# stm32-d40-platform.net
KiCad netlist of a schematic drawn in EAGLE
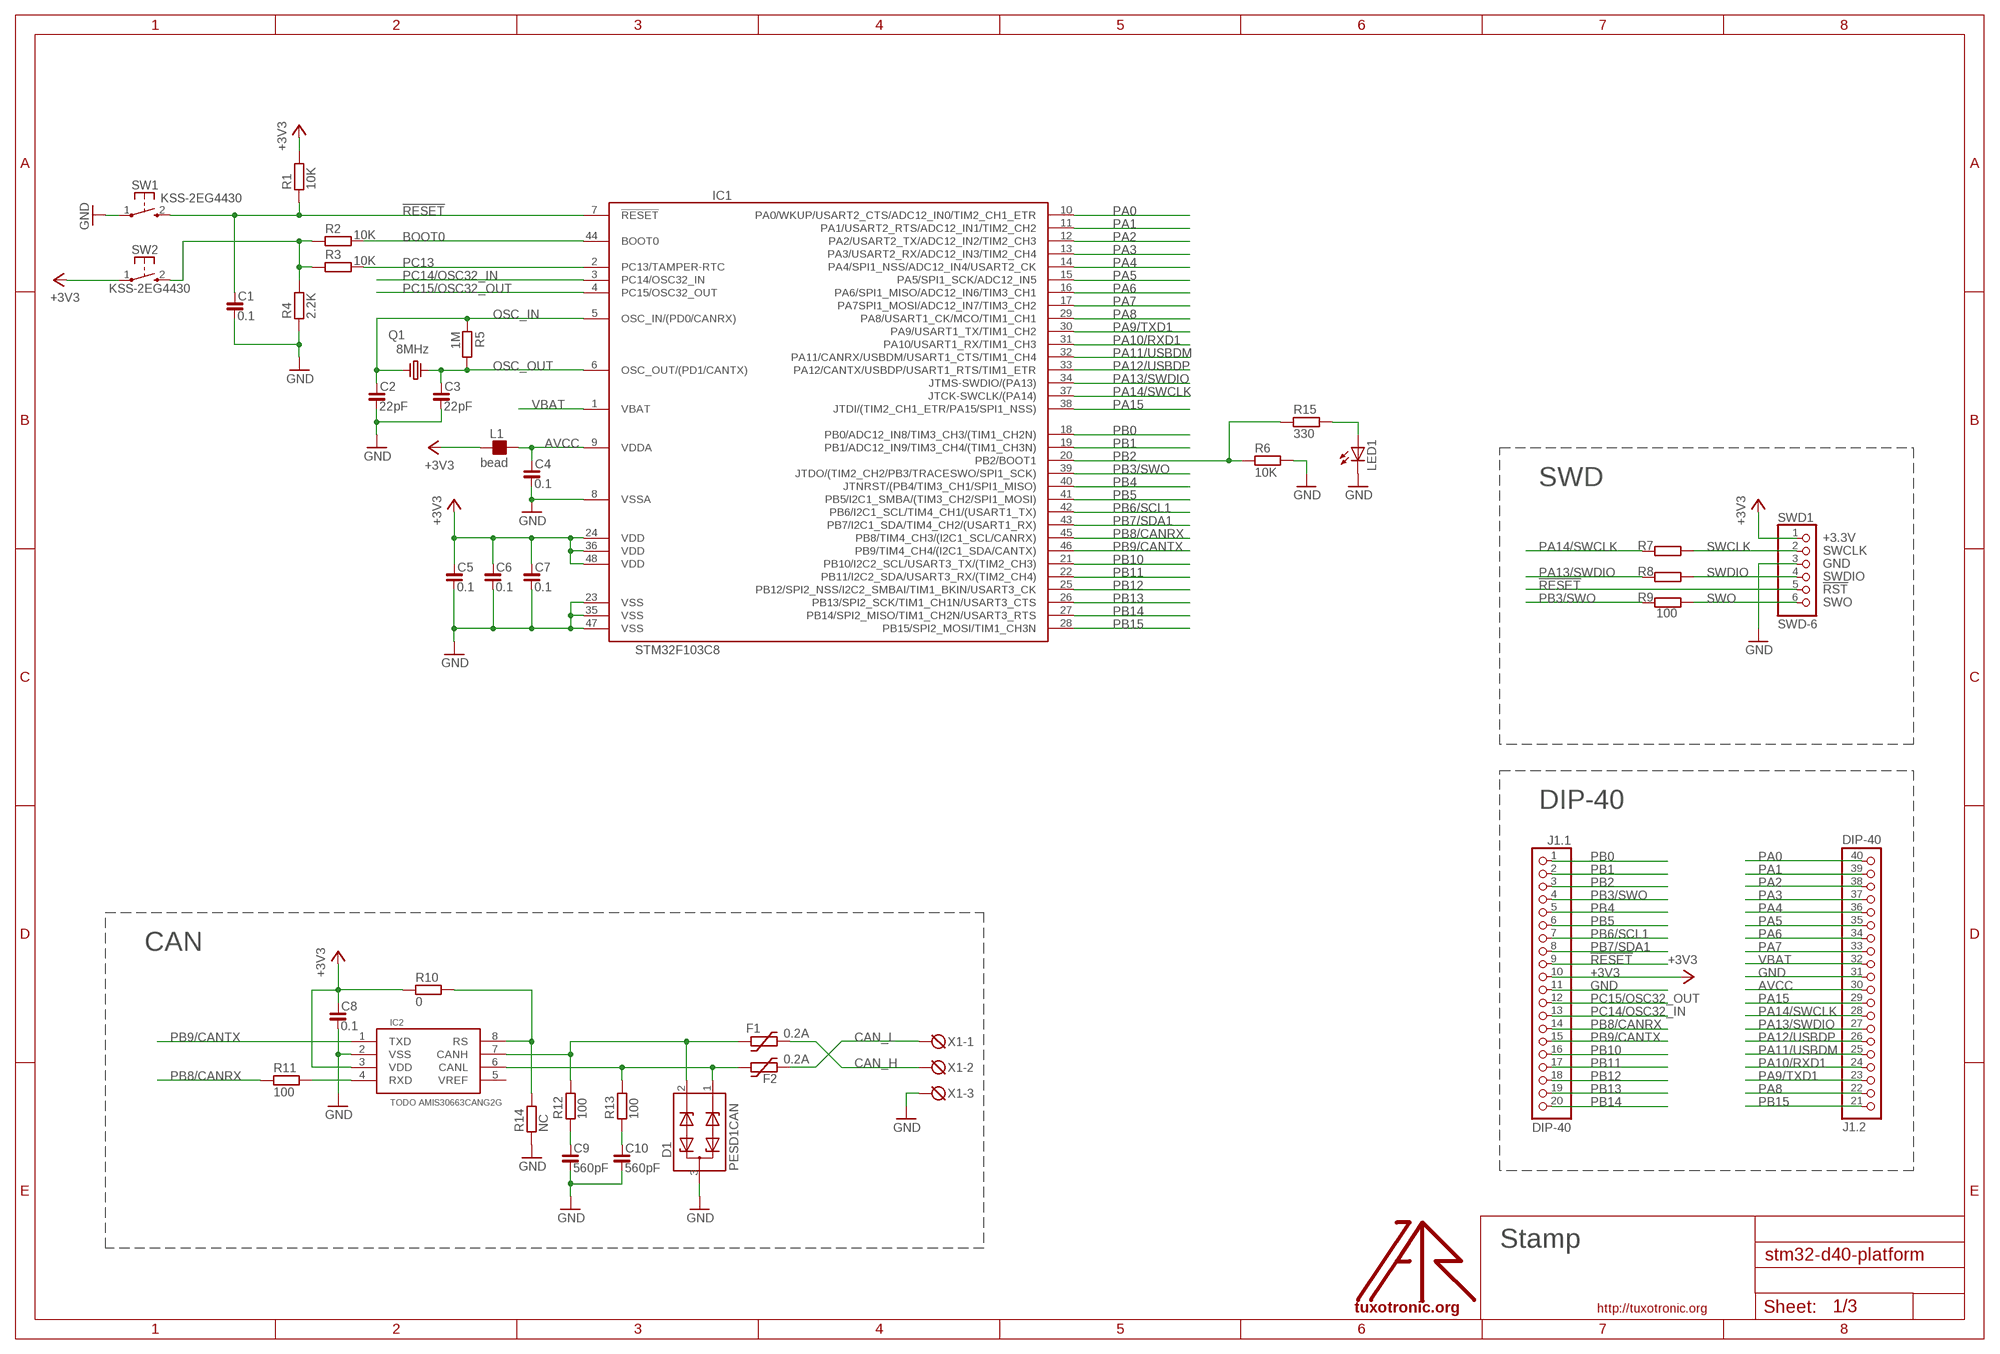
[diagram p0: schematic, sheet 1]
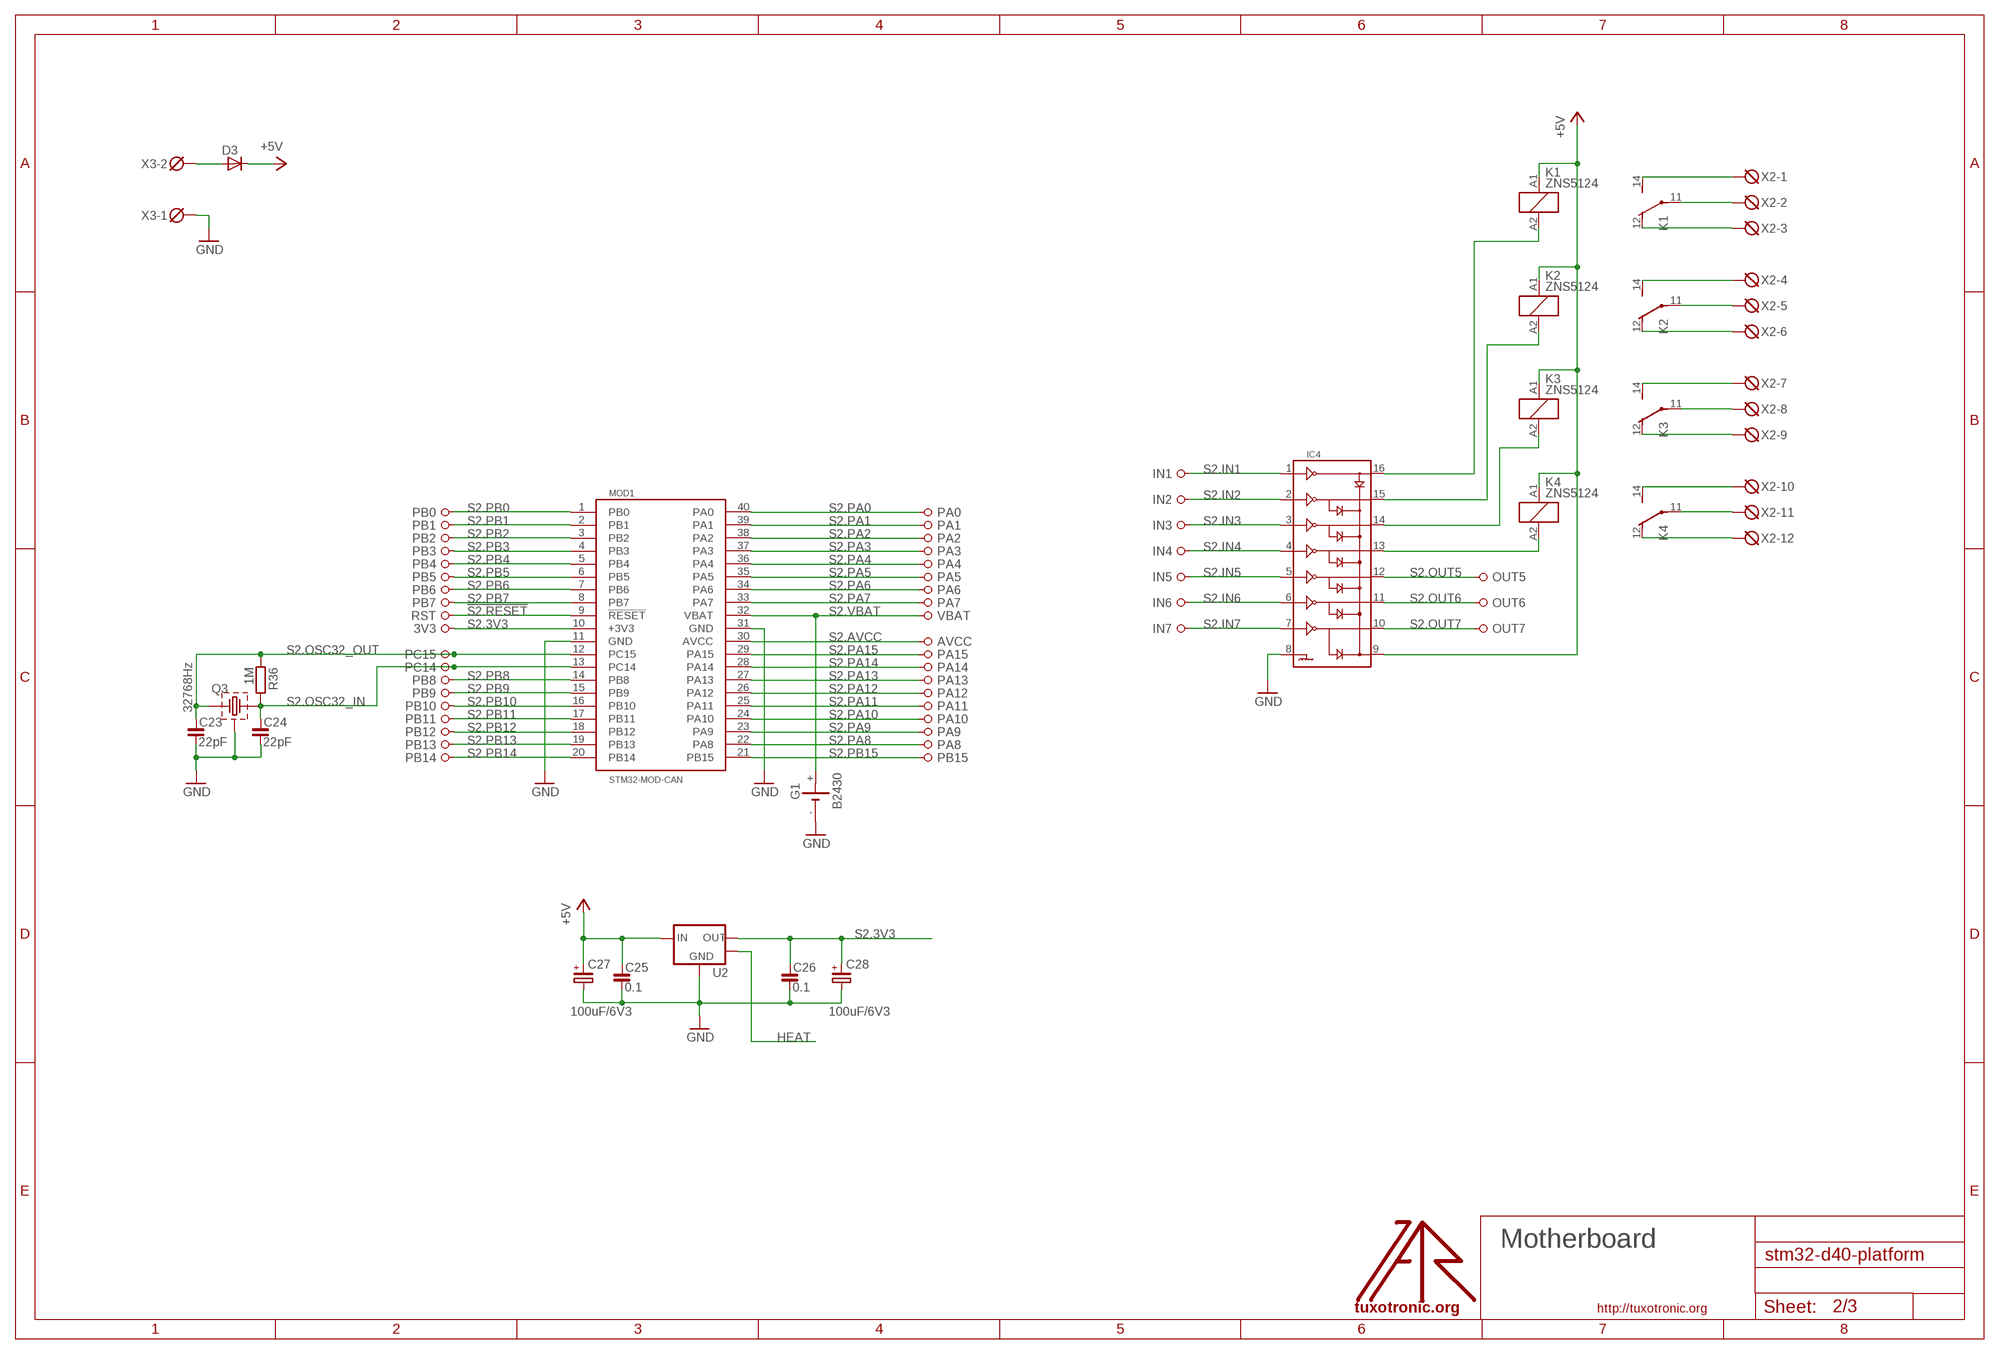
[diagram p1: schematic, sheet 2]
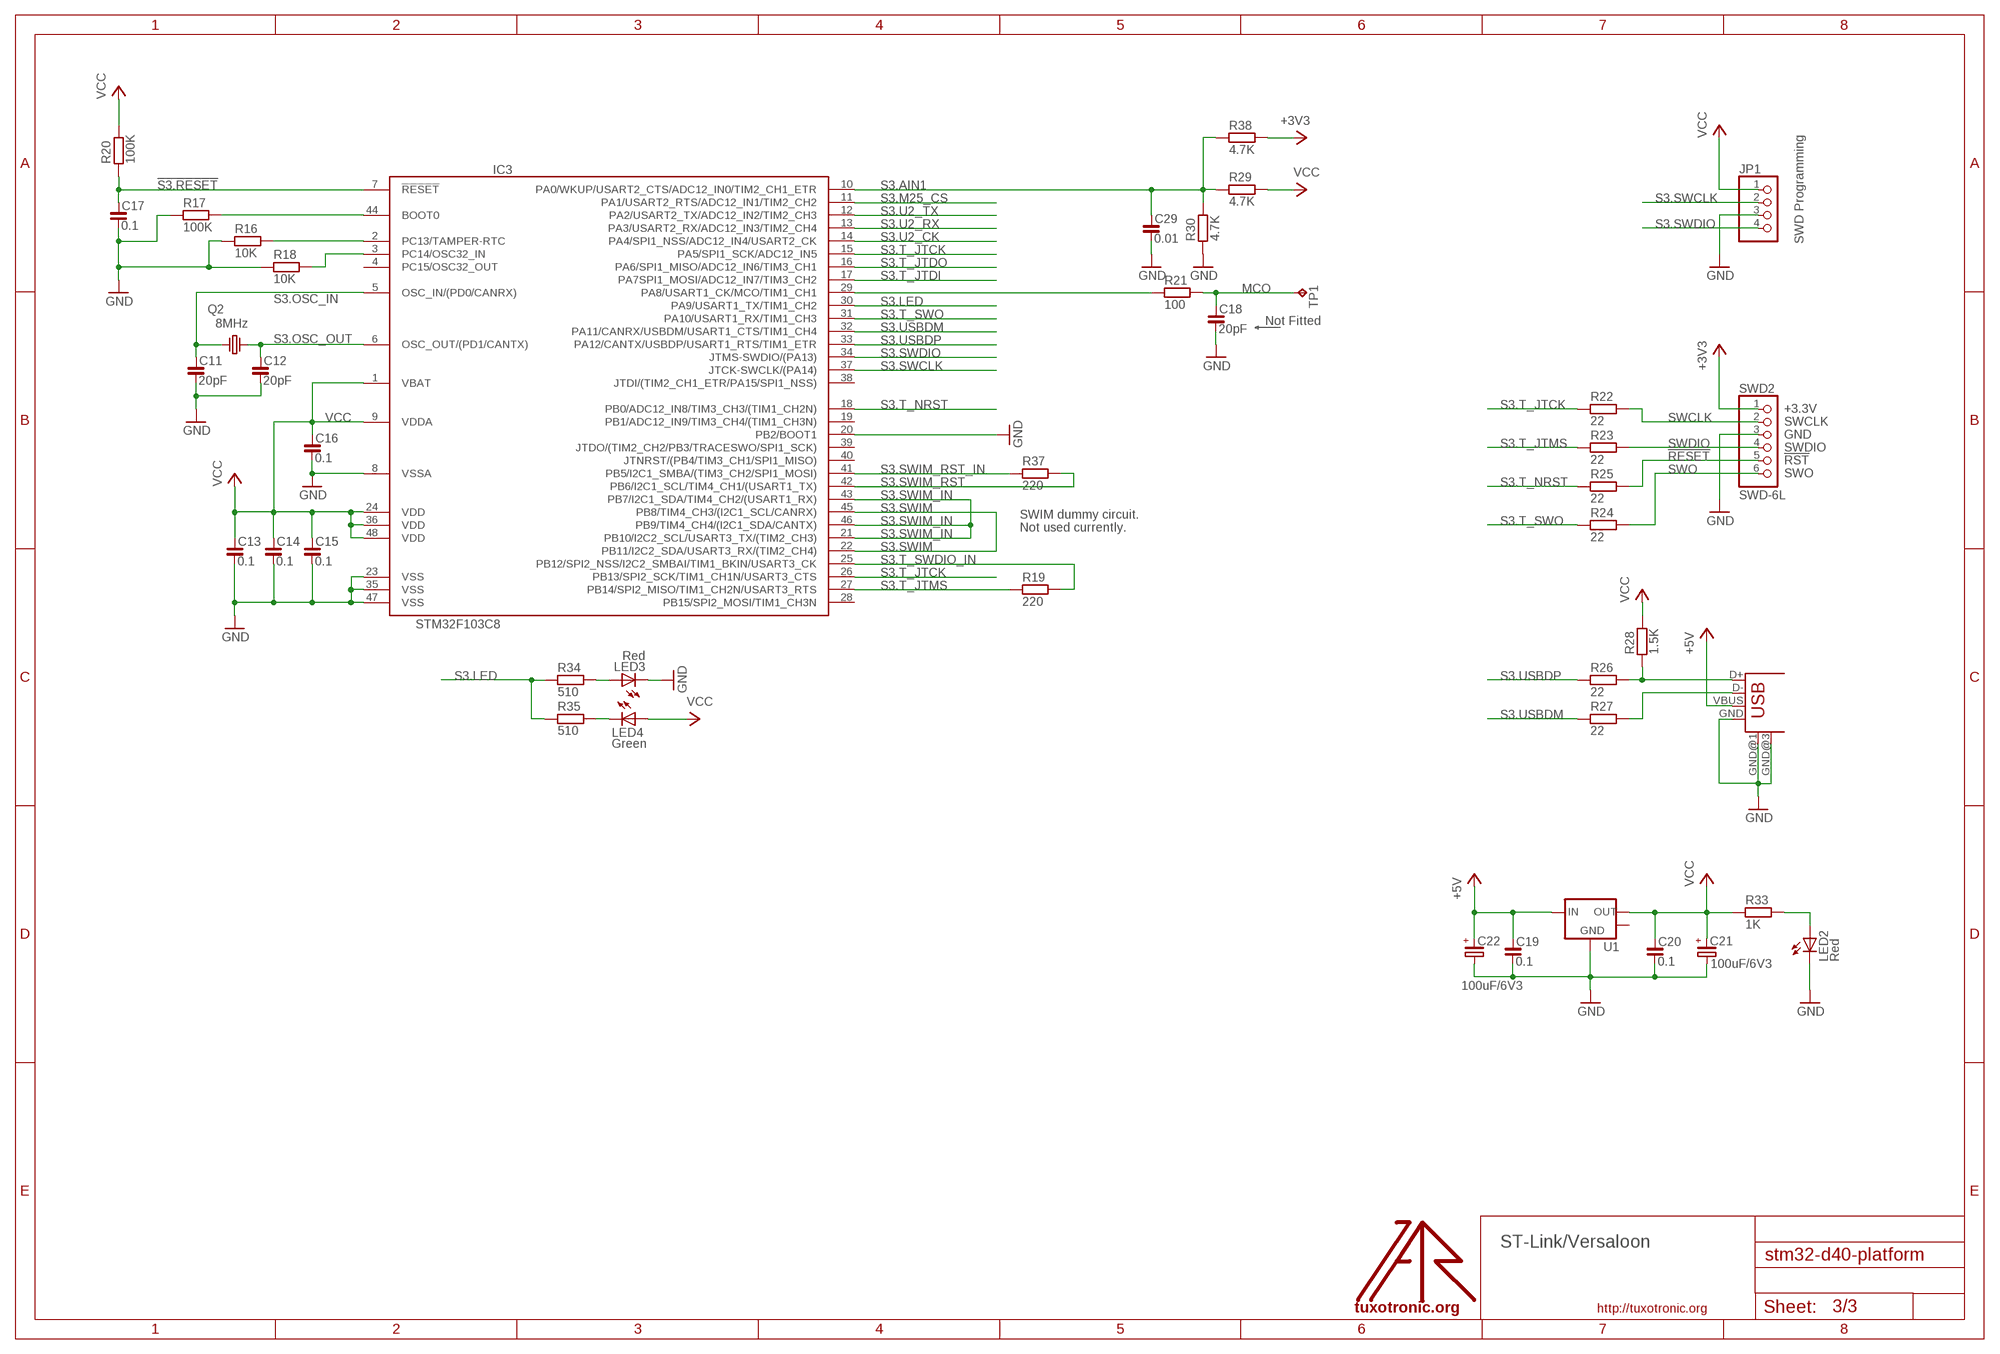
[diagram p2: schematic, sheet 3]

(export (version "E")
  (design (tool "Eeschema 10.0.6"))
  (components
    (comp (ref "C1")
      (value "0.1")
      (footprint "eagle-import:C0603")
      (libsource (lib "eagle-import") (part "C_0603"))
    )
    (comp (ref "C2")
      (value "22pF")
      (footprint "eagle-import:C0603")
      (libsource (lib "eagle-import") (part "C_0603"))
    )
    (comp (ref "C3")
      (value "22pF")
      (footprint "eagle-import:C0603")
      (libsource (lib "eagle-import") (part "C_0603"))
    )
    (comp (ref "C4")
      (value "0.1")
      (footprint "eagle-import:C0603")
      (libsource (lib "eagle-import") (part "C_0603"))
    )
    (comp (ref "C5")
      (value "0.1")
      (footprint "eagle-import:C0603")
      (libsource (lib "eagle-import") (part "C_0603"))
    )
    (comp (ref "C6")
      (value "0.1")
      (footprint "eagle-import:C0603")
      (libsource (lib "eagle-import") (part "C_0603"))
    )
    (comp (ref "C7")
      (value "0.1")
      (footprint "eagle-import:C0603")
      (libsource (lib "eagle-import") (part "C_0603"))
    )
    (comp (ref "C8")
      (value "0.1")
      (footprint "eagle-import:C0603")
      (libsource (lib "eagle-import") (part "C_0603"))
    )
    (comp (ref "C9")
      (value "560pF")
      (footprint "eagle-import:C0603")
      (libsource (lib "eagle-import") (part "C_0603"))
    )
    (comp (ref "C10")
      (value "560pF")
      (footprint "eagle-import:C0603")
      (libsource (lib "eagle-import") (part "C_0603"))
    )
    (comp (ref "D1")
      (value "PESD1CAN")
      (footprint "eagle-import:SOT23")
      (libsource (lib "eagle-import") (part "PESD1CAN"))
    )
    (comp (ref "F1")
      (value "0.2A")
      (footprint "eagle-import:1206L")
      (libsource (lib "eagle-import") (part "1206L"))
    )
    (comp (ref "F2")
      (value "0.2A")
      (footprint "eagle-import:1206L")
      (libsource (lib "eagle-import") (part "1206L"))
    )
    (comp (ref "IC1")
      (value "STM32F103C8")
      (footprint "eagle-import:LQFP48")
      (libsource (lib "eagle-import") (part "STM32F103C8"))
    )
    (comp (ref "IC2")
      (value "TODO AMIS30663CANG2G")
      (footprint "eagle-import:SO08")
      (libsource (lib "eagle-import") (part "SN65HVD230"))
    )
    (comp (ref "J1")
      (value "DIP-40")
      (footprint "eagle-import:DIP-40")
      (libsource (lib "eagle-import") (part "DIP-40"))
    )
    (comp (ref "L1")
      (value "bead")
      (footprint "eagle-import:L0603")
      (libsource (lib "eagle-import") (part "FB_0603"))
    )
    (comp (ref "LED1")
      (value "LEDCHIPLED_0603")
      (footprint "eagle-import:CHIPLED_0603")
      (libsource (lib "eagle-import") (part "LEDCHIPLED_0603"))
    )
    (comp (ref "Q1")
      (value "8MHz")
      (footprint "eagle-import:HC49_S")
      (libsource (lib "eagle-import") (part "CRYSTAL-HC49S"))
    )
    (comp (ref "R1")
      (value "10K")
      (footprint "eagle-import:R0603")
      (libsource (lib "eagle-import") (part "R_0603"))
    )
    (comp (ref "R2")
      (value "10K")
      (footprint "eagle-import:R0603")
      (libsource (lib "eagle-import") (part "R_0603"))
    )
    (comp (ref "R3")
      (value "10K")
      (footprint "eagle-import:R0603")
      (libsource (lib "eagle-import") (part "R_0603"))
    )
    (comp (ref "R4")
      (value "2.2K")
      (footprint "eagle-import:R0603")
      (libsource (lib "eagle-import") (part "R_0603"))
    )
    (comp (ref "R5")
      (value "1M")
      (footprint "eagle-import:R0603")
      (libsource (lib "eagle-import") (part "R_0603"))
    )
    (comp (ref "R6")
      (value "10K")
      (footprint "eagle-import:R0603")
      (libsource (lib "eagle-import") (part "R_0603"))
    )
    (comp (ref "R7")
      (value "100")
      (footprint "eagle-import:R0603")
      (libsource (lib "eagle-import") (part "R_0603"))
    )
    (comp (ref "R8")
      (value "100")
      (footprint "eagle-import:R0603")
      (libsource (lib "eagle-import") (part "R_0603"))
    )
    (comp (ref "R9")
      (value "100")
      (footprint "eagle-import:R0603")
      (libsource (lib "eagle-import") (part "R_0603"))
    )
    (comp (ref "R10")
      (value "0")
      (footprint "eagle-import:R0603")
      (libsource (lib "eagle-import") (part "R_0603"))
    )
    (comp (ref "R11")
      (value "100")
      (footprint "eagle-import:R0603")
      (libsource (lib "eagle-import") (part "R_0603"))
    )
    (comp (ref "R12")
      (value "100")
      (footprint "eagle-import:R0603")
      (libsource (lib "eagle-import") (part "R_0603"))
    )
    (comp (ref "R13")
      (value "100")
      (footprint "eagle-import:R0603")
      (libsource (lib "eagle-import") (part "R_0603"))
    )
    (comp (ref "R14")
      (value "NC")
      (footprint "eagle-import:R0603")
      (libsource (lib "eagle-import") (part "R_0603"))
    )
    (comp (ref "R15")
      (value "330")
      (footprint "eagle-import:R0603")
      (libsource (lib "eagle-import") (part "R_0603"))
    )
    (comp (ref "SW1")
      (value "KSS-2EG4430")
      (footprint "eagle-import:KSS-2EG4430")
      (libsource (lib "eagle-import") (part "KSS-2EG4430"))
    )
    (comp (ref "SW2")
      (value "KSS-2EG4430")
      (footprint "eagle-import:KSS-2EG4430")
      (libsource (lib "eagle-import") (part "KSS-2EG4430"))
    )
    (comp (ref "SWD1")
      (value "SWD-6")
      (footprint "eagle-import:JTAG6PIN")
      (libsource (lib "eagle-import") (part "SWD-6"))
    )
    (comp (ref "U$")
      (value "LOGO")
      (footprint "eagle-import:TT_LOGO")
      (libsource (lib "eagle-import") (part "LOGO"))
    )
    (comp (ref "X1")
      (value "DG3XX-03-3.5")
      (footprint "eagle-import:DG350-3.5-03P")
      (libsource (lib "eagle-import") (part "DG3XX-03-3.5"))
    )
    (comp (ref "C11")
      (value "20pF")
      (footprint "eagle-import:C0603")
      (libsource (lib "eagle-import") (part "C_0603"))
    )
    (comp (ref "C12")
      (value "20pF")
      (footprint "eagle-import:C0603")
      (libsource (lib "eagle-import") (part "C_0603"))
    )
    (comp (ref "C13")
      (value "0.1")
      (footprint "eagle-import:C0603")
      (libsource (lib "eagle-import") (part "C_0603"))
    )
    (comp (ref "C14")
      (value "0.1")
      (footprint "eagle-import:C0603")
      (libsource (lib "eagle-import") (part "C_0603"))
    )
    (comp (ref "C15")
      (value "0.1")
      (footprint "eagle-import:C0603")
      (libsource (lib "eagle-import") (part "C_0603"))
    )
    (comp (ref "C16")
      (value "0.1")
      (footprint "eagle-import:C0603")
      (libsource (lib "eagle-import") (part "C_0603"))
    )
    (comp (ref "C17")
      (value "0.1")
      (footprint "eagle-import:C0603")
      (libsource (lib "eagle-import") (part "C_0603"))
    )
    (comp (ref "C18")
      (value "20pF")
      (footprint "eagle-import:C0603")
      (libsource (lib "eagle-import") (part "C_0603"))
    )
    (comp (ref "C19")
      (value "0.1")
      (footprint "eagle-import:C0603")
      (libsource (lib "eagle-import") (part "C_0603"))
    )
    (comp (ref "C20")
      (value "0.1")
      (footprint "eagle-import:C0603")
      (libsource (lib "eagle-import") (part "C_0603"))
    )
    (comp (ref "C21")
      (value "100uF/6V3")
      (footprint "eagle-import:SMC_C")
      (libsource (lib "eagle-import") (part "CP_SMCC"))
    )
    (comp (ref "C22")
      (value "100uF/6V3")
      (footprint "eagle-import:SMC_C")
      (libsource (lib "eagle-import") (part "CP_SMCC"))
    )
    (comp (ref "C29")
      (value "0.01")
      (footprint "eagle-import:C0603")
      (libsource (lib "eagle-import") (part "C_0603"))
    )
    (comp (ref "IC3")
      (value "STM32F103C8")
      (footprint "eagle-import:LQFP48")
      (libsource (lib "eagle-import") (part "STM32F103C8"))
    )
    (comp (ref "JP1")
      (value "PINHD-1X4_2.00")
      (footprint "eagle-import:1X04M")
      (libsource (lib "eagle-import") (part "PINHD-1X4_2.00"))
    )
    (comp (ref "LED2")
      (value "Red")
      (footprint "eagle-import:CHIPLED_0603")
      (libsource (lib "eagle-import") (part "LEDCHIPLED_0603"))
    )
    (comp (ref "LED3")
      (value "Red")
      (footprint "eagle-import:CHIPLED_0603")
      (libsource (lib "eagle-import") (part "LEDCHIPLED_0603"))
    )
    (comp (ref "LED4")
      (value "Green")
      (footprint "eagle-import:CHIPLED_0603")
      (libsource (lib "eagle-import") (part "LEDCHIPLED_0603"))
    )
    (comp (ref "Q2")
      (value "8MHz")
      (footprint "eagle-import:HC49_S")
      (libsource (lib "eagle-import") (part "CRYSTAL-HC49S"))
    )
    (comp (ref "R16")
      (value "10K")
      (footprint "eagle-import:R0603")
      (libsource (lib "eagle-import") (part "R_0603"))
    )
    (comp (ref "R17")
      (value "100K")
      (footprint "eagle-import:R0603")
      (libsource (lib "eagle-import") (part "R_0603"))
    )
    (comp (ref "R18")
      (value "10K")
      (footprint "eagle-import:R0603")
      (libsource (lib "eagle-import") (part "R_0603"))
    )
    (comp (ref "R19")
      (value "220")
      (footprint "eagle-import:R0603")
      (libsource (lib "eagle-import") (part "R_0603"))
    )
    (comp (ref "R20")
      (value "100K")
      (footprint "eagle-import:R0603")
      (libsource (lib "eagle-import") (part "R_0603"))
    )
    (comp (ref "R21")
      (value "100")
      (footprint "eagle-import:R0603")
      (libsource (lib "eagle-import") (part "R_0603"))
    )
    (comp (ref "R22")
      (value "22")
      (footprint "eagle-import:R0603")
      (libsource (lib "eagle-import") (part "R_0603"))
    )
    (comp (ref "R23")
      (value "22")
      (footprint "eagle-import:R0603")
      (libsource (lib "eagle-import") (part "R_0603"))
    )
    (comp (ref "R24")
      (value "22")
      (footprint "eagle-import:R0603")
      (libsource (lib "eagle-import") (part "R_0603"))
    )
    (comp (ref "R25")
      (value "22")
      (footprint "eagle-import:R0603")
      (libsource (lib "eagle-import") (part "R_0603"))
    )
    (comp (ref "R26")
      (value "22")
      (footprint "eagle-import:R0603")
      (libsource (lib "eagle-import") (part "R_0603"))
    )
    (comp (ref "R27")
      (value "22")
      (footprint "eagle-import:R0603")
      (libsource (lib "eagle-import") (part "R_0603"))
    )
    (comp (ref "R28")
      (value "1.5K")
      (footprint "eagle-import:R0603")
      (libsource (lib "eagle-import") (part "R_0603"))
    )
    (comp (ref "R29")
      (value "4.7K")
      (footprint "eagle-import:R0603")
      (libsource (lib "eagle-import") (part "R_0603"))
    )
    (comp (ref "R30")
      (value "4.7K")
      (footprint "eagle-import:R0603")
      (libsource (lib "eagle-import") (part "R_0603"))
    )
    (comp (ref "R33")
      (value "1K")
      (footprint "eagle-import:R0603")
      (libsource (lib "eagle-import") (part "R_0603"))
    )
    (comp (ref "R34")
      (value "510")
      (footprint "eagle-import:R0603")
      (libsource (lib "eagle-import") (part "R_0603"))
    )
    (comp (ref "R35")
      (value "510")
      (footprint "eagle-import:R0603")
      (libsource (lib "eagle-import") (part "R_0603"))
    )
    (comp (ref "R37")
      (value "220")
      (footprint "eagle-import:R0603")
      (libsource (lib "eagle-import") (part "R_0603"))
    )
    (comp (ref "R38")
      (value "4.7K")
      (footprint "eagle-import:R0603")
      (libsource (lib "eagle-import") (part "R_0603"))
    )
    (comp (ref "S3.LOGO")
      (value "LOGO")
      (footprint "eagle-import:TT_LOGO")
      (libsource (lib "eagle-import") (part "LOGO"))
    )
    (comp (ref "SWD2")
      (value "SWD-6L")
      (footprint "eagle-import:SWD6PIN_L")
      (libsource (lib "eagle-import") (part "SWD-6L"))
    )
    (comp (ref "TP1")
      (value "TPB1,27")
      (footprint "eagle-import:B1,27")
      (libsource (lib "eagle-import") (part "TPB1,27"))
    )
    (comp (ref "U1")
      (value "LM1117-3.3")
      (footprint "eagle-import:SOT223")
      (libsource (lib "eagle-import") (part "LM1117-3.3"))
    )
    (comp (ref "USB1")
      (value "USB-MB-S2")
      (footprint "eagle-import:USB-MB-S2")
      (libsource (lib "eagle-import") (part "USB-MB-S2"))
    )
    (comp (ref "3V3")
      (value "PIN-1X1_2.54")
      (footprint "eagle-import:1X01")
      (libsource (lib "eagle-import") (part "PIN-1X1_2.54"))
    )
    (comp (ref "AVCC")
      (value "PIN-1X1_2.54")
      (footprint "eagle-import:1X01")
      (libsource (lib "eagle-import") (part "PIN-1X1_2.54"))
    )
    (comp (ref "C23")
      (value "22pF")
      (footprint "eagle-import:C0805")
      (libsource (lib "eagle-import") (part "C_0805"))
    )
    (comp (ref "C24")
      (value "22pF")
      (footprint "eagle-import:C0805")
      (libsource (lib "eagle-import") (part "C_0805"))
    )
    (comp (ref "C25")
      (value "0.1")
      (footprint "eagle-import:C0805")
      (libsource (lib "eagle-import") (part "C_0805"))
    )
    (comp (ref "C26")
      (value "0.1")
      (footprint "eagle-import:C0805")
      (libsource (lib "eagle-import") (part "C_0805"))
    )
    (comp (ref "C27")
      (value "100uF/6V3")
      (footprint "eagle-import:CE-035X080")
      (libsource (lib "eagle-import") (part "CP_E-035X080"))
    )
    (comp (ref "C28")
      (value "100uF/6V3")
      (footprint "eagle-import:CE-035X080")
      (libsource (lib "eagle-import") (part "CP_E-035X080"))
    )
    (comp (ref "D3")
      (value "D-SMB")
      (footprint "eagle-import:SMB")
      (libsource (lib "eagle-import") (part "D-SMB"))
    )
    (comp (ref "G1")
      (value "B2430")
      (footprint "eagle-import:B2430")
      (libsource (lib "eagle-import") (part "B2430"))
    )
    (comp (ref "IC4")
      (value "ULN2003D")
      (footprint "eagle-import:SO16")
      (libsource (lib "eagle-import") (part "ULN2003D"))
    )
    (comp (ref "IN1")
      (value "PIN-1X1_2.54")
      (footprint "eagle-import:1X01")
      (libsource (lib "eagle-import") (part "PIN-1X1_2.54"))
    )
    (comp (ref "IN2")
      (value "PIN-1X1_2.54")
      (footprint "eagle-import:1X01")
      (libsource (lib "eagle-import") (part "PIN-1X1_2.54"))
    )
    (comp (ref "IN3")
      (value "PIN-1X1_2.54")
      (footprint "eagle-import:1X01")
      (libsource (lib "eagle-import") (part "PIN-1X1_2.54"))
    )
    (comp (ref "IN4")
      (value "PIN-1X1_2.54")
      (footprint "eagle-import:1X01")
      (libsource (lib "eagle-import") (part "PIN-1X1_2.54"))
    )
    (comp (ref "IN5")
      (value "PIN-1X1_2.54")
      (footprint "eagle-import:1X01")
      (libsource (lib "eagle-import") (part "PIN-1X1_2.54"))
    )
    (comp (ref "IN6")
      (value "PIN-1X1_2.54")
      (footprint "eagle-import:1X01")
      (libsource (lib "eagle-import") (part "PIN-1X1_2.54"))
    )
    (comp (ref "IN7")
      (value "PIN-1X1_2.54")
      (footprint "eagle-import:1X01")
      (libsource (lib "eagle-import") (part "PIN-1X1_2.54"))
    )
    (comp (ref "K1")
      (value "ZNS5124")
      (footprint "eagle-import:ZN5")
      (libsource (lib "eagle-import") (part "ZNS5124"))
    )
    (comp (ref "K2")
      (value "ZNS5124")
      (footprint "eagle-import:ZN5")
      (libsource (lib "eagle-import") (part "ZNS5124"))
    )
    (comp (ref "K3")
      (value "ZNS5124")
      (footprint "eagle-import:ZN5")
      (libsource (lib "eagle-import") (part "ZNS5124"))
    )
    (comp (ref "K4")
      (value "ZNS5124")
      (footprint "eagle-import:ZN5")
      (libsource (lib "eagle-import") (part "ZNS5124"))
    )
    (comp (ref "MOD1")
      (value "STM32-MOD-CAN")
      (footprint "eagle-import:DIL40")
      (libsource (lib "eagle-import") (part "STM32-MOD-CAN"))
    )
    (comp (ref "OUT5")
      (value "PIN-1X1_2.54")
      (footprint "eagle-import:1X01")
      (libsource (lib "eagle-import") (part "PIN-1X1_2.54"))
    )
    (comp (ref "OUT6")
      (value "PIN-1X1_2.54")
      (footprint "eagle-import:1X01")
      (libsource (lib "eagle-import") (part "PIN-1X1_2.54"))
    )
    (comp (ref "OUT7")
      (value "PIN-1X1_2.54")
      (footprint "eagle-import:1X01")
      (libsource (lib "eagle-import") (part "PIN-1X1_2.54"))
    )
    (comp (ref "PA0")
      (value "PIN-1X1_2.54")
      (footprint "eagle-import:1X01")
      (libsource (lib "eagle-import") (part "PIN-1X1_2.54"))
    )
    (comp (ref "PA1")
      (value "PIN-1X1_2.54")
      (footprint "eagle-import:1X01")
      (libsource (lib "eagle-import") (part "PIN-1X1_2.54"))
    )
    (comp (ref "PA2")
      (value "PIN-1X1_2.54")
      (footprint "eagle-import:1X01")
      (libsource (lib "eagle-import") (part "PIN-1X1_2.54"))
    )
    (comp (ref "PA3")
      (value "PIN-1X1_2.54")
      (footprint "eagle-import:1X01")
      (libsource (lib "eagle-import") (part "PIN-1X1_2.54"))
    )
    (comp (ref "PA4")
      (value "PIN-1X1_2.54")
      (footprint "eagle-import:1X01")
      (libsource (lib "eagle-import") (part "PIN-1X1_2.54"))
    )
    (comp (ref "PA5")
      (value "PIN-1X1_2.54")
      (footprint "eagle-import:1X01")
      (libsource (lib "eagle-import") (part "PIN-1X1_2.54"))
    )
    (comp (ref "PA6")
      (value "PIN-1X1_2.54")
      (footprint "eagle-import:1X01")
      (libsource (lib "eagle-import") (part "PIN-1X1_2.54"))
    )
    (comp (ref "PA7")
      (value "PIN-1X1_2.54")
      (footprint "eagle-import:1X01")
      (libsource (lib "eagle-import") (part "PIN-1X1_2.54"))
    )
    (comp (ref "PA8")
      (value "PIN-1X1_2.54")
      (footprint "eagle-import:1X01")
      (libsource (lib "eagle-import") (part "PIN-1X1_2.54"))
    )
    (comp (ref "PA9")
      (value "PIN-1X1_2.54")
      (footprint "eagle-import:1X01")
      (libsource (lib "eagle-import") (part "PIN-1X1_2.54"))
    )
    (comp (ref "PA10")
      (value "PIN-1X1_2.54")
      (footprint "eagle-import:1X01")
      (libsource (lib "eagle-import") (part "PIN-1X1_2.54"))
    )
    (comp (ref "PA11")
      (value "PIN-1X1_2.54")
      (footprint "eagle-import:1X01")
      (libsource (lib "eagle-import") (part "PIN-1X1_2.54"))
    )
    (comp (ref "PA12")
      (value "PIN-1X1_2.54")
      (footprint "eagle-import:1X01")
      (libsource (lib "eagle-import") (part "PIN-1X1_2.54"))
    )
    (comp (ref "PA13")
      (value "PIN-1X1_2.54")
      (footprint "eagle-import:1X01")
      (libsource (lib "eagle-import") (part "PIN-1X1_2.54"))
    )
    (comp (ref "PA14")
      (value "PIN-1X1_2.54")
      (footprint "eagle-import:1X01")
      (libsource (lib "eagle-import") (part "PIN-1X1_2.54"))
    )
    (comp (ref "PA15")
      (value "PIN-1X1_2.54")
      (footprint "eagle-import:1X01")
      (libsource (lib "eagle-import") (part "PIN-1X1_2.54"))
    )
    (comp (ref "PB0")
      (value "PIN-1X1_2.54")
      (footprint "eagle-import:1X01")
      (libsource (lib "eagle-import") (part "PIN-1X1_2.54"))
    )
    (comp (ref "PB1")
      (value "PIN-1X1_2.54")
      (footprint "eagle-import:1X01")
      (libsource (lib "eagle-import") (part "PIN-1X1_2.54"))
    )
    (comp (ref "PB2")
      (value "PIN-1X1_2.54")
      (footprint "eagle-import:1X01")
      (libsource (lib "eagle-import") (part "PIN-1X1_2.54"))
    )
    (comp (ref "PB3")
      (value "PIN-1X1_2.54")
      (footprint "eagle-import:1X01")
      (libsource (lib "eagle-import") (part "PIN-1X1_2.54"))
    )
    (comp (ref "PB4")
      (value "PIN-1X1_2.54")
      (footprint "eagle-import:1X01")
      (libsource (lib "eagle-import") (part "PIN-1X1_2.54"))
    )
    (comp (ref "PB5")
      (value "PIN-1X1_2.54")
      (footprint "eagle-import:1X01")
      (libsource (lib "eagle-import") (part "PIN-1X1_2.54"))
    )
    (comp (ref "PB6")
      (value "PIN-1X1_2.54")
      (footprint "eagle-import:1X01")
      (libsource (lib "eagle-import") (part "PIN-1X1_2.54"))
    )
    (comp (ref "PB7")
      (value "PIN-1X1_2.54")
      (footprint "eagle-import:1X01")
      (libsource (lib "eagle-import") (part "PIN-1X1_2.54"))
    )
    (comp (ref "PB8")
      (value "PIN-1X1_2.54")
      (footprint "eagle-import:1X01")
      (libsource (lib "eagle-import") (part "PIN-1X1_2.54"))
    )
    (comp (ref "PB9")
      (value "PIN-1X1_2.54")
      (footprint "eagle-import:1X01")
      (libsource (lib "eagle-import") (part "PIN-1X1_2.54"))
    )
    (comp (ref "PB10")
      (value "PIN-1X1_2.54")
      (footprint "eagle-import:1X01")
      (libsource (lib "eagle-import") (part "PIN-1X1_2.54"))
    )
    (comp (ref "PB11")
      (value "PIN-1X1_2.54")
      (footprint "eagle-import:1X01")
      (libsource (lib "eagle-import") (part "PIN-1X1_2.54"))
    )
    (comp (ref "PB12")
      (value "PIN-1X1_2.54")
      (footprint "eagle-import:1X01")
      (libsource (lib "eagle-import") (part "PIN-1X1_2.54"))
    )
    (comp (ref "PB13")
      (value "PIN-1X1_2.54")
      (footprint "eagle-import:1X01")
      (libsource (lib "eagle-import") (part "PIN-1X1_2.54"))
    )
    (comp (ref "PB14")
      (value "PIN-1X1_2.54")
      (footprint "eagle-import:1X01")
      (libsource (lib "eagle-import") (part "PIN-1X1_2.54"))
    )
    (comp (ref "PB15")
      (value "PIN-1X1_2.54")
      (footprint "eagle-import:1X01")
      (libsource (lib "eagle-import") (part "PIN-1X1_2.54"))
    )
    (comp (ref "PC14")
      (value "PIN-1X1_2.54")
      (footprint "eagle-import:1X01")
      (libsource (lib "eagle-import") (part "PIN-1X1_2.54"))
    )
    (comp (ref "PC15")
      (value "PIN-1X1_2.54")
      (footprint "eagle-import:1X01")
      (libsource (lib "eagle-import") (part "PIN-1X1_2.54"))
    )
    (comp (ref "Q3")
      (value "32768Hz")
      (footprint "eagle-import:TC38H-G")
      (libsource (lib "eagle-import") (part "CRSTL3-"))
    )
    (comp (ref "R36")
      (value "1M")
      (footprint "eagle-import:R0805")
      (libsource (lib "eagle-import") (part "R_0805"))
    )
    (comp (ref "RST")
      (value "PIN-1X1_2.54")
      (footprint "eagle-import:1X01")
      (libsource (lib "eagle-import") (part "PIN-1X1_2.54"))
    )
    (comp (ref "U$1")
      (value "LOGO")
      (footprint "eagle-import:TT_LOGO")
      (libsource (lib "eagle-import") (part "LOGO"))
    )
    (comp (ref "U2")
      (value "LM1117-3.3")
      (footprint "eagle-import:SOT223")
      (libsource (lib "eagle-import") (part "LM1117-3.3"))
    )
    (comp (ref "VBAT")
      (value "PIN-1X1_2.54")
      (footprint "eagle-import:1X01")
      (libsource (lib "eagle-import") (part "PIN-1X1_2.54"))
    )
    (comp (ref "X2")
      (value "DG3XX-12-5.0")
      (footprint "eagle-import:DG306-5.0-12P")
      (libsource (lib "eagle-import") (part "DG3XX-12-5.0"))
    )
    (comp (ref "X3")
      (value "DG3XX-02-5.0")
      (footprint "eagle-import:DG306-5.0-02P")
      (libsource (lib "eagle-import") (part "DG3XX-02-5.0"))
    )
  )
  (nets
    (net (code "1") (name "+3V3") (class "Default")
      (node (ref "C5") (pin "1") (pinfunction "1_1") (pintype "passive"))
      (node (ref "C6") (pin "1") (pinfunction "1_1") (pintype "passive"))
      (node (ref "C7") (pin "1") (pinfunction "1_1") (pintype "passive"))
      (node (ref "C8") (pin "1") (pinfunction "1_1") (pintype "passive"))
      (node (ref "IC1") (pin "24") (pinfunction "VDD_24") (pintype "power_in"))
      (node (ref "IC1") (pin "36") (pinfunction "VDD_36") (pintype "power_in"))
      (node (ref "IC1") (pin "48") (pinfunction "VDD_48") (pintype "power_in"))
      (node (ref "IC2") (pin "3") (pinfunction "VDD_3") (pintype "power_in"))
      (node (ref "J1") (pin "10") (pinfunction "10_10") (pintype "passive"))
      (node (ref "L1") (pin "1") (pinfunction "1_1") (pintype "passive"))
      (node (ref "R1") (pin "2") (pinfunction "2_2") (pintype "passive"))
      (node (ref "R10") (pin "1") (pinfunction "1_1") (pintype "passive"))
      (node (ref "R38") (pin "2") (pinfunction "2_2") (pintype "passive"))
      (node (ref "SW2") (pin "1") (pinfunction "P_1") (pintype "passive"))
      (node (ref "SWD1") (pin "1") (pinfunction "1_1") (pintype "passive"))
      (node (ref "SWD2") (pin "1") (pinfunction "1_1") (pintype "passive"))
    )
    (net (code "2") (name "+5V") (class "Default")
      (node (ref "C19") (pin "1") (pinfunction "1_1") (pintype "passive"))
      (node (ref "C22") (pin "+") (pinfunction "+_+") (pintype "passive"))
      (node (ref "C25") (pin "1") (pinfunction "1_1") (pintype "passive"))
      (node (ref "C27") (pin "+") (pinfunction "+_+") (pintype "passive"))
      (node (ref "D3") (pin "C") (pinfunction "C_C") (pintype "passive"))
      (node (ref "IC4") (pin "9") (pinfunction "9_9") (pintype "power_in"))
      (node (ref "K1") (pin "A1") (pinfunction "1_A1") (pintype "passive"))
      (node (ref "K2") (pin "A1") (pinfunction "1_A1") (pintype "passive"))
      (node (ref "K3") (pin "A1") (pinfunction "1_A1") (pintype "passive"))
      (node (ref "K4") (pin "A1") (pinfunction "1_A1") (pintype "passive"))
      (node (ref "U1") (pin "3") (pinfunction "IN_3") (pintype "power_in"))
      (node (ref "U2") (pin "3") (pinfunction "IN_3") (pintype "power_in"))
      (node (ref "USB1") (pin "VBUS") (pinfunction "VBUS_VBUS") (pintype "bidirectional"))
    )
    (net (code "3") (name "AVCC") (class "Default")
      (node (ref "C4") (pin "1") (pinfunction "1_1") (pintype "passive"))
      (node (ref "IC1") (pin "9") (pinfunction "VDDA_9") (pintype "power_in"))
      (node (ref "J1") (pin "30") (pinfunction "10_30") (pintype "passive"))
      (node (ref "L1") (pin "2") (pinfunction "2_2") (pintype "passive"))
    )
    (net (code "4") (name "BOOT0") (class "Default")
      (node (ref "IC1") (pin "44") (pinfunction "BOOT0_44") (pintype "input"))
      (node (ref "R2") (pin "2") (pinfunction "2_2") (pintype "passive"))
    )
    (net (code "5") (name "CAN_H") (class "Default")
      (node (ref "F1") (pin "P$2") (pinfunction "2_P$2") (pintype "passive"))
      (node (ref "X1") (pin "2") (pinfunction "KL_2") (pintype "passive"))
    )
    (net (code "6") (name "CAN_L") (class "Default")
      (node (ref "F2") (pin "P$2") (pinfunction "2_P$2") (pintype "passive"))
      (node (ref "X1") (pin "1") (pinfunction "KL_1") (pintype "passive"))
    )
    (net (code "7") (name "GND") (class "Default")
      (node (ref "C1") (pin "2") (pinfunction "2_2") (pintype "passive"))
      (node (ref "C10") (pin "2") (pinfunction "2_2") (pintype "passive"))
      (node (ref "C11") (pin "2") (pinfunction "2_2") (pintype "passive"))
      (node (ref "C12") (pin "2") (pinfunction "2_2") (pintype "passive"))
      (node (ref "C13") (pin "2") (pinfunction "2_2") (pintype "passive"))
      (node (ref "C14") (pin "2") (pinfunction "2_2") (pintype "passive"))
      (node (ref "C15") (pin "2") (pinfunction "2_2") (pintype "passive"))
      (node (ref "C16") (pin "2") (pinfunction "2_2") (pintype "passive"))
      (node (ref "C17") (pin "2") (pinfunction "2_2") (pintype "passive"))
      (node (ref "C18") (pin "2") (pinfunction "2_2") (pintype "passive"))
      (node (ref "C19") (pin "2") (pinfunction "2_2") (pintype "passive"))
      (node (ref "C2") (pin "2") (pinfunction "2_2") (pintype "passive"))
      (node (ref "C20") (pin "2") (pinfunction "2_2") (pintype "passive"))
      (node (ref "C21") (pin "-") (pinfunction "-_-") (pintype "passive"))
      (node (ref "C22") (pin "-") (pinfunction "-_-") (pintype "passive"))
      (node (ref "C23") (pin "2") (pinfunction "2_2") (pintype "passive"))
      (node (ref "C24") (pin "2") (pinfunction "2_2") (pintype "passive"))
      (node (ref "C25") (pin "2") (pinfunction "2_2") (pintype "passive"))
      (node (ref "C26") (pin "2") (pinfunction "2_2") (pintype "passive"))
      (node (ref "C27") (pin "-") (pinfunction "-_-") (pintype "passive"))
      (node (ref "C28") (pin "-") (pinfunction "-_-") (pintype "passive"))
      (node (ref "C29") (pin "2") (pinfunction "2_2") (pintype "passive"))
      (node (ref "C3") (pin "2") (pinfunction "2_2") (pintype "passive"))
      (node (ref "C4") (pin "2") (pinfunction "2_2") (pintype "passive"))
      (node (ref "C5") (pin "2") (pinfunction "2_2") (pintype "passive"))
      (node (ref "C6") (pin "2") (pinfunction "2_2") (pintype "passive"))
      (node (ref "C7") (pin "2") (pinfunction "2_2") (pintype "passive"))
      (node (ref "C8") (pin "2") (pinfunction "2_2") (pintype "passive"))
      (node (ref "C9") (pin "2") (pinfunction "2_2") (pintype "passive"))
      (node (ref "D1") (pin "3") (pinfunction "3_3") (pintype "passive"))
      (node (ref "G1") (pin "-") (pinfunction "-_-") (pintype "passive"))
      (node (ref "IC1") (pin "23") (pinfunction "VSS_23") (pintype "power_in"))
      (node (ref "IC1") (pin "35") (pinfunction "VSS_35") (pintype "power_in"))
      (node (ref "IC1") (pin "47") (pinfunction "VSS_47") (pintype "power_in"))
      (node (ref "IC1") (pin "8") (pinfunction "VSSA_8") (pintype "power_in"))
      (node (ref "IC2") (pin "2") (pinfunction "VSS_2") (pintype "power_in"))
      (node (ref "IC3") (pin "20") (pinfunction "PB2/BOOT1_20") (pintype "bidirectional"))
      (node (ref "IC3") (pin "23") (pinfunction "VSS_23") (pintype "power_in"))
      (node (ref "IC3") (pin "35") (pinfunction "VSS_35") (pintype "power_in"))
      (node (ref "IC3") (pin "47") (pinfunction "VSS_47") (pintype "power_in"))
      (node (ref "IC3") (pin "8") (pinfunction "VSSA_8") (pintype "power_in"))
      (node (ref "IC4") (pin "8") (pinfunction "8_8") (pintype "power_in"))
      (node (ref "J1") (pin "11") (pinfunction "11_11") (pintype "passive"))
      (node (ref "J1") (pin "31") (pinfunction "11_31") (pintype "passive"))
      (node (ref "JP1") (pin "3") (pinfunction "3_3") (pintype "passive"))
      (node (ref "LED1") (pin "C") (pinfunction "C_C") (pintype "passive"))
      (node (ref "LED2") (pin "C") (pinfunction "C_C") (pintype "passive"))
      (node (ref "LED3") (pin "C") (pinfunction "C_C") (pintype "passive"))
      (node (ref "MOD1") (pin "11") (pinfunction "GND_11") (pintype "power_in"))
      (node (ref "MOD1") (pin "31") (pinfunction "GND_31") (pintype "power_in"))
      (node (ref "Q3") (pin "GND") (pinfunction "P$1_GND") (pintype "passive"))
      (node (ref "R14") (pin "1") (pinfunction "1_1") (pintype "passive"))
      (node (ref "R16") (pin "1") (pinfunction "1_1") (pintype "passive"))
      (node (ref "R17") (pin "1") (pinfunction "1_1") (pintype "passive"))
      (node (ref "R18") (pin "1") (pinfunction "1_1") (pintype "passive"))
      (node (ref "R30") (pin "1") (pinfunction "1_1") (pintype "passive"))
      (node (ref "R4") (pin "1") (pinfunction "1_1") (pintype "passive"))
      (node (ref "R6") (pin "2") (pinfunction "2_2") (pintype "passive"))
      (node (ref "SW1") (pin "1") (pinfunction "P_1") (pintype "passive"))
      (node (ref "SWD1") (pin "3") (pinfunction "3_3") (pintype "passive"))
      (node (ref "SWD2") (pin "3") (pinfunction "3_3") (pintype "passive"))
      (node (ref "U1") (pin "1") (pinfunction "GND_1") (pintype "power_in"))
      (node (ref "U2") (pin "1") (pinfunction "GND_1") (pintype "power_in"))
      (node (ref "USB1") (pin "GND") (pinfunction "GND_GND") (pintype "bidirectional"))
      (node (ref "USB1") (pin "GND@1") (pinfunction "GND_GND@1") (pintype "bidirectional"))
      (node (ref "USB1") (pin "GND@3") (pinfunction "GND_GND@3") (pintype "bidirectional"))
      (node (ref "X1") (pin "3") (pinfunction "KL_3") (pintype "passive"))
      (node (ref "X3") (pin "1") (pinfunction "KL_1") (pintype "passive"))
    )
    (net (code "8") (name "HEAT") (class "Default")
      (node (ref "U2") (pin "4") (pinfunction "MASS_4") (pintype "passive"))
    )
    (net (code "9") (name "MCO") (class "Default")
      (node (ref "C18") (pin "1") (pinfunction "1_1") (pintype "passive"))
      (node (ref "R21") (pin "2") (pinfunction "2_2") (pintype "passive"))
      (node (ref "TP1") (pin "PP") (pinfunction "TP_PP") (pintype "input"))
    )
    (net (code "10") (name "Net-(C9-Pad1)") (class "Default")
      (node (ref "C9") (pin "1") (pinfunction "1_1") (pintype "passive"))
      (node (ref "R12") (pin "1") (pinfunction "1_1") (pintype "passive"))
    )
    (net (code "11") (name "Net-(C10-Pad1)") (class "Default")
      (node (ref "C10") (pin "1") (pinfunction "1_1") (pintype "passive"))
      (node (ref "R13") (pin "1") (pinfunction "1_1") (pintype "passive"))
    )
    (net (code "12") (name "Net-(F1-1)") (class "Default")
      (node (ref "D1") (pin "2") (pinfunction "2_2") (pintype "passive"))
      (node (ref "F1") (pin "P$1") (pinfunction "1_P$1") (pintype "passive"))
      (node (ref "IC2") (pin "7") (pinfunction "CANH_7") (pintype "bidirectional"))
      (node (ref "R12") (pin "2") (pinfunction "2_2") (pintype "passive"))
    )
    (net (code "13") (name "Net-(F2-1)") (class "Default")
      (node (ref "D1") (pin "1") (pinfunction "1_1") (pintype "passive"))
      (node (ref "F2") (pin "P$1") (pinfunction "1_P$1") (pintype "passive"))
      (node (ref "IC2") (pin "6") (pinfunction "CANL_6") (pintype "bidirectional"))
      (node (ref "R13") (pin "2") (pinfunction "2_2") (pintype "passive"))
    )
    (net (code "14") (name "Net-(IC2-RS)") (class "Default")
      (node (ref "IC2") (pin "8") (pinfunction "RS_8") (pintype "input"))
      (node (ref "R10") (pin "2") (pinfunction "2_2") (pintype "passive"))
      (node (ref "R14") (pin "2") (pinfunction "2_2") (pintype "passive"))
    )
    (net (code "15") (name "Net-(IC2-RXD)") (class "Default")
      (node (ref "IC2") (pin "4") (pinfunction "RXD_4") (pintype "output"))
      (node (ref "R11") (pin "2") (pinfunction "2_2") (pintype "passive"))
    )
    (net (code "16") (name "Net-(IC3-BOOT0)") (class "Default")
      (node (ref "IC3") (pin "44") (pinfunction "BOOT0_44") (pintype "input"))
      (node (ref "R17") (pin "2") (pinfunction "2_2") (pintype "passive"))
    )
    (net (code "17") (name "Net-(IC3-PA8{slash}USART1_CK{slash}MCO{slash}TIM1_CH1)") (class "Default")
      (node (ref "IC3") (pin "29") (pinfunction "PA8/USART1_CK/MCO/TIM1_CH1_29") (pintype "bidirectional"))
      (node (ref "R21") (pin "1") (pinfunction "1_1") (pintype "passive"))
    )
    (net (code "18") (name "Net-(IC3-PC13{slash}TAMPER-RTC)") (class "Default")
      (node (ref "IC3") (pin "2") (pinfunction "PC13/TAMPER-RTC_2") (pintype "bidirectional"))
      (node (ref "R16") (pin "2") (pinfunction "2_2") (pintype "passive"))
    )
    (net (code "19") (name "Net-(IC3-PC14{slash}OSC32_IN)") (class "Default")
      (node (ref "IC3") (pin "3") (pinfunction "PC14/OSC32_IN_3") (pintype "bidirectional"))
      (node (ref "R18") (pin "2") (pinfunction "2_2") (pintype "passive"))
    )
    (net (code "20") (name "Net-(K1A-2)") (class "Default")
      (node (ref "IC4") (pin "16") (pinfunction "16_16") (pintype "open_collector"))
      (node (ref "K1") (pin "A2") (pinfunction "2_A2") (pintype "passive"))
    )
    (net (code "21") (name "Net-(K1B-O)") (class "Default")
      (node (ref "K1") (pin "12") (pinfunction "O_12") (pintype "passive"))
      (node (ref "X2") (pin "3") (pinfunction "KL_3") (pintype "passive"))
    )
    (net (code "22") (name "Net-(K1B-P)") (class "Default")
      (node (ref "K1") (pin "11") (pinfunction "P_11") (pintype "passive"))
      (node (ref "X2") (pin "2") (pinfunction "KL_2") (pintype "passive"))
    )
    (net (code "23") (name "Net-(K1B-S)") (class "Default")
      (node (ref "K1") (pin "14") (pinfunction "S_14") (pintype "passive"))
      (node (ref "X2") (pin "1") (pinfunction "KL_1") (pintype "passive"))
    )
    (net (code "24") (name "Net-(K2A-2)") (class "Default")
      (node (ref "IC4") (pin "15") (pinfunction "15_15") (pintype "open_collector"))
      (node (ref "K2") (pin "A2") (pinfunction "2_A2") (pintype "passive"))
    )
    (net (code "25") (name "Net-(K2B-O)") (class "Default")
      (node (ref "K2") (pin "12") (pinfunction "O_12") (pintype "passive"))
      (node (ref "X2") (pin "6") (pinfunction "KL_6") (pintype "passive"))
    )
    (net (code "26") (name "Net-(K2B-P)") (class "Default")
      (node (ref "K2") (pin "11") (pinfunction "P_11") (pintype "passive"))
      (node (ref "X2") (pin "5") (pinfunction "KL_5") (pintype "passive"))
    )
    (net (code "27") (name "Net-(K2B-S)") (class "Default")
      (node (ref "K2") (pin "14") (pinfunction "S_14") (pintype "passive"))
      (node (ref "X2") (pin "4") (pinfunction "KL_4") (pintype "passive"))
    )
    (net (code "28") (name "Net-(K3A-2)") (class "Default")
      (node (ref "IC4") (pin "14") (pinfunction "14_14") (pintype "open_collector"))
      (node (ref "K3") (pin "A2") (pinfunction "2_A2") (pintype "passive"))
    )
    (net (code "29") (name "Net-(K3B-O)") (class "Default")
      (node (ref "K3") (pin "12") (pinfunction "O_12") (pintype "passive"))
      (node (ref "X2") (pin "9") (pinfunction "KL_9") (pintype "passive"))
    )
    (net (code "30") (name "Net-(K3B-P)") (class "Default")
      (node (ref "K3") (pin "11") (pinfunction "P_11") (pintype "passive"))
      (node (ref "X2") (pin "8") (pinfunction "KL_8") (pintype "passive"))
    )
    (net (code "31") (name "Net-(K3B-S)") (class "Default")
      (node (ref "K3") (pin "14") (pinfunction "S_14") (pintype "passive"))
      (node (ref "X2") (pin "7") (pinfunction "KL_7") (pintype "passive"))
    )
    (net (code "32") (name "Net-(K4A-2)") (class "Default")
      (node (ref "IC4") (pin "13") (pinfunction "13_13") (pintype "open_collector"))
      (node (ref "K4") (pin "A2") (pinfunction "2_A2") (pintype "passive"))
    )
    (net (code "33") (name "Net-(K4B-O)") (class "Default")
      (node (ref "K4") (pin "12") (pinfunction "O_12") (pintype "passive"))
      (node (ref "X2") (pin "12") (pinfunction "KL_12") (pintype "passive"))
    )
    (net (code "34") (name "Net-(K4B-P)") (class "Default")
      (node (ref "K4") (pin "11") (pinfunction "P_11") (pintype "passive"))
      (node (ref "X2") (pin "11") (pinfunction "KL_11") (pintype "passive"))
    )
    (net (code "35") (name "Net-(K4B-S)") (class "Default")
      (node (ref "K4") (pin "14") (pinfunction "S_14") (pintype "passive"))
      (node (ref "X2") (pin "10") (pinfunction "KL_10") (pintype "passive"))
    )
    (net (code "36") (name "Net-(LED1-PadA)") (class "Default")
      (node (ref "LED1") (pin "A") (pinfunction "A_A") (pintype "passive"))
      (node (ref "R15") (pin "2") (pinfunction "2_2") (pintype "passive"))
    )
    (net (code "37") (name "Net-(LED2-PadA)") (class "Default")
      (node (ref "LED2") (pin "A") (pinfunction "A_A") (pintype "passive"))
      (node (ref "R33") (pin "2") (pinfunction "2_2") (pintype "passive"))
    )
    (net (code "38") (name "Net-(LED3-PadA)") (class "Default")
      (node (ref "LED3") (pin "A") (pinfunction "A_A") (pintype "passive"))
      (node (ref "R34") (pin "2") (pinfunction "2_2") (pintype "passive"))
    )
    (net (code "39") (name "Net-(LED4-PadC)") (class "Default")
      (node (ref "LED4") (pin "C") (pinfunction "C_C") (pintype "passive"))
      (node (ref "R35") (pin "2") (pinfunction "2_2") (pintype "passive"))
    )
    (net (code "40") (name "Net-(R26-Pad2)") (class "Default")
      (node (ref "R26") (pin "2") (pinfunction "2_2") (pintype "passive"))
      (node (ref "R28") (pin "1") (pinfunction "1_1") (pintype "passive"))
      (node (ref "USB1") (pin "D+") (pinfunction "D+_D+") (pintype "bidirectional"))
    )
    (net (code "41") (name "Net-(R27-Pad2)") (class "Default")
      (node (ref "R27") (pin "2") (pinfunction "2_2") (pintype "passive"))
      (node (ref "USB1") (pin "D-") (pinfunction "D-_D-") (pintype "bidirectional"))
    )
    (net (code "42") (name "Net-(SW2-S)") (class "Default")
      (node (ref "R2") (pin "1") (pinfunction "1_1") (pintype "passive"))
      (node (ref "R3") (pin "1") (pinfunction "1_1") (pintype "passive"))
      (node (ref "R4") (pin "2") (pinfunction "2_2") (pintype "passive"))
      (node (ref "SW2") (pin "2") (pinfunction "S_2") (pintype "passive"))
    )
    (net (code "43") (name "Net-(X3B-KL)") (class "Default")
      (node (ref "D3") (pin "A") (pinfunction "A_A") (pintype "passive"))
      (node (ref "X3") (pin "2") (pinfunction "KL_2") (pintype "passive"))
    )
    (net (code "44") (name "OSC_IN") (class "Default")
      (node (ref "C2") (pin "1") (pinfunction "1_1") (pintype "passive"))
      (node (ref "IC1") (pin "5") (pinfunction "OSC_IN/(PD0/CANRX)_5") (pintype "input"))
      (node (ref "Q1") (pin "1") (pinfunction "1_1") (pintype "passive"))
      (node (ref "R5") (pin "1") (pinfunction "1_1") (pintype "passive"))
    )
    (net (code "45") (name "OSC_OUT") (class "Default")
      (node (ref "C3") (pin "1") (pinfunction "1_1") (pintype "passive"))
      (node (ref "IC1") (pin "6") (pinfunction "OSC_OUT/(PD1/CANTX)_6") (pintype "output"))
      (node (ref "Q1") (pin "2") (pinfunction "2_2") (pintype "passive"))
      (node (ref "R5") (pin "2") (pinfunction "2_2") (pintype "passive"))
    )
    (net (code "46") (name "PA0") (class "Default")
      (node (ref "IC1") (pin "10") (pinfunction "PA0/WKUP/USART2_CTS/ADC12_IN0/TIM2_CH1_ETR_10") (pintype "bidirectional"))
      (node (ref "J1") (pin "40") (pinfunction "20_40") (pintype "passive"))
    )
    (net (code "47") (name "PA1") (class "Default")
      (node (ref "IC1") (pin "11") (pinfunction "PA1/USART2_RTS/ADC12_IN1/TIM2_CH2_11") (pintype "bidirectional"))
      (node (ref "J1") (pin "39") (pinfunction "19_39") (pintype "passive"))
    )
    (net (code "48") (name "PA2") (class "Default")
      (node (ref "IC1") (pin "12") (pinfunction "PA2/USART2_TX/ADC12_IN2/TIM2_CH3_12") (pintype "bidirectional"))
      (node (ref "J1") (pin "38") (pinfunction "18_38") (pintype "passive"))
    )
    (net (code "49") (name "PA3") (class "Default")
      (node (ref "IC1") (pin "13") (pinfunction "PA3/USART2_RX/ADC12_IN3/TIM2_CH4_13") (pintype "bidirectional"))
      (node (ref "J1") (pin "37") (pinfunction "17_37") (pintype "passive"))
    )
    (net (code "50") (name "PA4") (class "Default")
      (node (ref "IC1") (pin "14") (pinfunction "PA4/SPI1_NSS/ADC12_IN4/USART2_CK_14") (pintype "bidirectional"))
      (node (ref "J1") (pin "36") (pinfunction "16_36") (pintype "passive"))
    )
    (net (code "51") (name "PA5") (class "Default")
      (node (ref "IC1") (pin "15") (pinfunction "PA5/SPI1_SCK/ADC12_IN5_15") (pintype "bidirectional"))
      (node (ref "J1") (pin "35") (pinfunction "15_35") (pintype "passive"))
    )
    (net (code "52") (name "PA6") (class "Default")
      (node (ref "IC1") (pin "16") (pinfunction "PA6/SPI1_MISO/ADC12_IN6/TIM3_CH1_16") (pintype "bidirectional"))
      (node (ref "J1") (pin "34") (pinfunction "14_34") (pintype "passive"))
    )
    (net (code "53") (name "PA7") (class "Default")
      (node (ref "IC1") (pin "17") (pinfunction "PA7SPI1_MOSI/ADC12_IN7/TIM3_CH2_17") (pintype "bidirectional"))
      (node (ref "J1") (pin "33") (pinfunction "13_33") (pintype "passive"))
    )
    (net (code "54") (name "PA8") (class "Default")
      (node (ref "IC1") (pin "29") (pinfunction "PA8/USART1_CK/MCO/TIM1_CH1_29") (pintype "bidirectional"))
      (node (ref "J1") (pin "22") (pinfunction "2_22") (pintype "passive"))
    )
    (net (code "55") (name "PA9{slash}TXD1") (class "Default")
      (node (ref "IC1") (pin "30") (pinfunction "PA9/USART1_TX/TIM1_CH2_30") (pintype "bidirectional"))
      (node (ref "J1") (pin "23") (pinfunction "3_23") (pintype "passive"))
    )
    (net (code "56") (name "PA10{slash}RXD1") (class "Default")
      (node (ref "IC1") (pin "31") (pinfunction "PA10/USART1_RX/TIM1_CH3_31") (pintype "bidirectional"))
      (node (ref "J1") (pin "24") (pinfunction "4_24") (pintype "passive"))
    )
    (net (code "57") (name "PA11{slash}USBDM") (class "Default")
      (node (ref "IC1") (pin "32") (pinfunction "PA11/CANRX/USBDM/USART1_CTS/TIM1_CH4_32") (pintype "bidirectional"))
      (node (ref "J1") (pin "25") (pinfunction "5_25") (pintype "passive"))
    )
    (net (code "58") (name "PA12{slash}USBDP") (class "Default")
      (node (ref "IC1") (pin "33") (pinfunction "PA12/CANTX/USBDP/USART1_RTS/TIM1_ETR_33") (pintype "bidirectional"))
      (node (ref "J1") (pin "26") (pinfunction "6_26") (pintype "passive"))
    )
    (net (code "59") (name "PA13{slash}SWDIO") (class "Default")
      (node (ref "IC1") (pin "34") (pinfunction "JTMS-SWDIO/(PA13)_34") (pintype "bidirectional"))
      (node (ref "J1") (pin "27") (pinfunction "7_27") (pintype "passive"))
      (node (ref "R8") (pin "1") (pinfunction "1_1") (pintype "passive"))
    )
    (net (code "60") (name "PA14{slash}SWCLK") (class "Default")
      (node (ref "IC1") (pin "37") (pinfunction "JTCK-SWCLK/(PA14)_37") (pintype "bidirectional"))
      (node (ref "J1") (pin "28") (pinfunction "8_28") (pintype "passive"))
      (node (ref "R7") (pin "1") (pinfunction "1_1") (pintype "passive"))
    )
    (net (code "61") (name "PA15") (class "Default")
      (node (ref "IC1") (pin "38") (pinfunction "JTDI/(TIM2_CH1_ETR/PA15/SPI1_NSS)_38") (pintype "bidirectional"))
      (node (ref "J1") (pin "29") (pinfunction "9_29") (pintype "passive"))
    )
    (net (code "62") (name "PB0") (class "Default")
      (node (ref "IC1") (pin "18") (pinfunction "PB0/ADC12_IN8/TIM3_CH3/(TIM1_CH2N)_18") (pintype "bidirectional"))
      (node (ref "J1") (pin "1") (pinfunction "1_1") (pintype "passive"))
    )
    (net (code "63") (name "PB1") (class "Default")
      (node (ref "IC1") (pin "19") (pinfunction "PB1/ADC12_IN9/TIM3_CH4/(TIM1_CH3N)_19") (pintype "bidirectional"))
      (node (ref "J1") (pin "2") (pinfunction "2_2") (pintype "passive"))
    )
    (net (code "64") (name "PB2") (class "Default")
      (node (ref "IC1") (pin "20") (pinfunction "PB2/BOOT1_20") (pintype "bidirectional"))
      (node (ref "J1") (pin "3") (pinfunction "3_3") (pintype "passive"))
      (node (ref "R15") (pin "1") (pinfunction "1_1") (pintype "passive"))
      (node (ref "R6") (pin "1") (pinfunction "1_1") (pintype "passive"))
    )
    (net (code "65") (name "PB3{slash}SWO") (class "Default")
      (node (ref "IC1") (pin "39") (pinfunction "JTDO/(TIM2_CH2/PB3/TRACESWO/SPI1_SCK)_39") (pintype "bidirectional"))
      (node (ref "J1") (pin "4") (pinfunction "4_4") (pintype "passive"))
      (node (ref "R9") (pin "1") (pinfunction "1_1") (pintype "passive"))
    )
    (net (code "66") (name "PB4") (class "Default")
      (node (ref "IC1") (pin "40") (pinfunction "JTNRST/(PB4/TIM3_CH1/SPI1_MISO)_40") (pintype "bidirectional"))
      (node (ref "J1") (pin "5") (pinfunction "5_5") (pintype "passive"))
    )
    (net (code "67") (name "PB5") (class "Default")
      (node (ref "IC1") (pin "41") (pinfunction "PB5/I2C1_SMBA/(TIM3_CH2/SPI1_MOSI)_41") (pintype "bidirectional"))
      (node (ref "J1") (pin "6") (pinfunction "6_6") (pintype "passive"))
    )
    (net (code "68") (name "PB6{slash}SCL1") (class "Default")
      (node (ref "IC1") (pin "42") (pinfunction "PB6/I2C1_SCL/TIM4_CH1/(USART1_TX)_42") (pintype "bidirectional"))
      (node (ref "J1") (pin "7") (pinfunction "7_7") (pintype "passive"))
    )
    (net (code "69") (name "PB7{slash}SDA1") (class "Default")
      (node (ref "IC1") (pin "43") (pinfunction "PB7/I2C1_SDA/TIM4_CH2/(USART1_RX)_43") (pintype "bidirectional"))
      (node (ref "J1") (pin "8") (pinfunction "8_8") (pintype "passive"))
    )
    (net (code "70") (name "PB8{slash}CANRX") (class "Default")
      (node (ref "IC1") (pin "45") (pinfunction "PB8/TIM4_CH3/(I2C1_SCL/CANRX)_45") (pintype "bidirectional"))
      (node (ref "J1") (pin "14") (pinfunction "14_14") (pintype "passive"))
      (node (ref "R11") (pin "1") (pinfunction "1_1") (pintype "passive"))
    )
    (net (code "71") (name "PB9{slash}CANTX") (class "Default")
      (node (ref "IC1") (pin "46") (pinfunction "PB9/TIM4_CH4/(I2C1_SDA/CANTX)_46") (pintype "bidirectional"))
      (node (ref "IC2") (pin "1") (pinfunction "TXD_1") (pintype "input"))
      (node (ref "J1") (pin "15") (pinfunction "15_15") (pintype "passive"))
    )
    (net (code "72") (name "PB10") (class "Default")
      (node (ref "IC1") (pin "21") (pinfunction "PB10/I2C2_SCL/USART3_TX/(TIM2_CH3)_21") (pintype "bidirectional"))
      (node (ref "J1") (pin "16") (pinfunction "16_16") (pintype "passive"))
    )
    (net (code "73") (name "PB11") (class "Default")
      (node (ref "IC1") (pin "22") (pinfunction "PB11/I2C2_SDA/USART3_RX/(TIM2_CH4)_22") (pintype "bidirectional"))
      (node (ref "J1") (pin "17") (pinfunction "17_17") (pintype "passive"))
    )
    (net (code "74") (name "PB12") (class "Default")
      (node (ref "IC1") (pin "25") (pinfunction "PB12/SPI2_NSS/I2C2_SMBAI/TIM1_BKIN/USART3_CK_25") (pintype "bidirectional"))
      (node (ref "J1") (pin "18") (pinfunction "18_18") (pintype "passive"))
    )
    (net (code "75") (name "PB13") (class "Default")
      (node (ref "IC1") (pin "26") (pinfunction "PB13/SPI2_SCK/TIM1_CH1N/USART3_CTS_26") (pintype "bidirectional"))
      (node (ref "J1") (pin "19") (pinfunction "19_19") (pintype "passive"))
    )
    (net (code "76") (name "PB14") (class "Default")
      (node (ref "IC1") (pin "27") (pinfunction "PB14/SPI2_MISO/TIM1_CH2N/USART3_RTS_27") (pintype "bidirectional"))
      (node (ref "J1") (pin "20") (pinfunction "20_20") (pintype "passive"))
    )
    (net (code "77") (name "PB15") (class "Default")
      (node (ref "IC1") (pin "28") (pinfunction "PB15/SPI2_MOSI/TIM1_CH3N_28") (pintype "bidirectional"))
      (node (ref "J1") (pin "21") (pinfunction "1_21") (pintype "passive"))
    )
    (net (code "78") (name "PC13") (class "Default")
      (node (ref "IC1") (pin "2") (pinfunction "PC13/TAMPER-RTC_2") (pintype "bidirectional"))
      (node (ref "R3") (pin "2") (pinfunction "2_2") (pintype "passive"))
    )
    (net (code "79") (name "PC14{slash}OSC32_IN") (class "Default")
      (node (ref "IC1") (pin "3") (pinfunction "PC14/OSC32_IN_3") (pintype "bidirectional"))
      (node (ref "J1") (pin "13") (pinfunction "13_13") (pintype "passive"))
    )
    (net (code "80") (name "PC15{slash}OSC32_OUT") (class "Default")
      (node (ref "IC1") (pin "4") (pinfunction "PC15/OSC32_OUT_4") (pintype "bidirectional"))
      (node (ref "J1") (pin "12") (pinfunction "12_12") (pintype "passive"))
    )
    (net (code "81") (name "S2.3V3") (class "Default")
      (node (ref "3V3") (pin "1") (pinfunction "1_1") (pintype "passive"))
      (node (ref "C26") (pin "1") (pinfunction "1_1") (pintype "passive"))
      (node (ref "C28") (pin "+") (pinfunction "+_+") (pintype "passive"))
      (node (ref "MOD1") (pin "10") (pinfunction "+3V3_10") (pintype "power_in"))
      (node (ref "U2") (pin "2") (pinfunction "OUT_2") (pintype "power_in"))
    )
    (net (code "82") (name "S2.AVCC") (class "Default")
      (node (ref "AVCC") (pin "1") (pinfunction "1_1") (pintype "passive"))
      (node (ref "MOD1") (pin "30") (pinfunction "AVCC_30") (pintype "power_in"))
    )
    (net (code "83") (name "S2.IN1") (class "Default")
      (node (ref "IC4") (pin "1") (pinfunction "1_1") (pintype "input"))
      (node (ref "IN1") (pin "1") (pinfunction "1_1") (pintype "passive"))
    )
    (net (code "84") (name "S2.IN2") (class "Default")
      (node (ref "IC4") (pin "2") (pinfunction "2_2") (pintype "input"))
      (node (ref "IN2") (pin "1") (pinfunction "1_1") (pintype "passive"))
    )
    (net (code "85") (name "S2.IN3") (class "Default")
      (node (ref "IC4") (pin "3") (pinfunction "3_3") (pintype "input"))
      (node (ref "IN3") (pin "1") (pinfunction "1_1") (pintype "passive"))
    )
    (net (code "86") (name "S2.IN4") (class "Default")
      (node (ref "IC4") (pin "4") (pinfunction "4_4") (pintype "input"))
      (node (ref "IN4") (pin "1") (pinfunction "1_1") (pintype "passive"))
    )
    (net (code "87") (name "S2.IN5") (class "Default")
      (node (ref "IC4") (pin "5") (pinfunction "5_5") (pintype "input"))
      (node (ref "IN5") (pin "1") (pinfunction "1_1") (pintype "passive"))
    )
    (net (code "88") (name "S2.IN6") (class "Default")
      (node (ref "IC4") (pin "6") (pinfunction "6_6") (pintype "input"))
      (node (ref "IN6") (pin "1") (pinfunction "1_1") (pintype "passive"))
    )
    (net (code "89") (name "S2.IN7") (class "Default")
      (node (ref "IC4") (pin "7") (pinfunction "7_7") (pintype "input"))
      (node (ref "IN7") (pin "1") (pinfunction "1_1") (pintype "passive"))
    )
    (net (code "90") (name "S2.OSC32_IN") (class "Default")
      (node (ref "C24") (pin "1") (pinfunction "1_1") (pintype "passive"))
      (node (ref "MOD1") (pin "13") (pinfunction "PC14_13") (pintype "bidirectional"))
      (node (ref "PC14") (pin "1") (pinfunction "1_1") (pintype "passive"))
      (node (ref "Q3") (pin "2") (pinfunction "2_2") (pintype "passive"))
      (node (ref "R36") (pin "2") (pinfunction "2_2") (pintype "passive"))
    )
    (net (code "91") (name "S2.OSC32_OUT") (class "Default")
      (node (ref "C23") (pin "1") (pinfunction "1_1") (pintype "passive"))
      (node (ref "MOD1") (pin "12") (pinfunction "PC15_12") (pintype "bidirectional"))
      (node (ref "PC15") (pin "1") (pinfunction "1_1") (pintype "passive"))
      (node (ref "Q3") (pin "1") (pinfunction "1_1") (pintype "passive"))
      (node (ref "R36") (pin "1") (pinfunction "1_1") (pintype "passive"))
    )
    (net (code "92") (name "S2.OUT5") (class "Default")
      (node (ref "IC4") (pin "12") (pinfunction "12_12") (pintype "open_collector"))
      (node (ref "OUT5") (pin "1") (pinfunction "1_1") (pintype "passive"))
    )
    (net (code "93") (name "S2.OUT6") (class "Default")
      (node (ref "IC4") (pin "11") (pinfunction "11_11") (pintype "open_collector"))
      (node (ref "OUT6") (pin "1") (pinfunction "1_1") (pintype "passive"))
    )
    (net (code "94") (name "S2.OUT7") (class "Default")
      (node (ref "IC4") (pin "10") (pinfunction "10_10") (pintype "open_collector"))
      (node (ref "OUT7") (pin "1") (pinfunction "1_1") (pintype "passive"))
    )
    (net (code "95") (name "S2.PA0") (class "Default")
      (node (ref "MOD1") (pin "40") (pinfunction "PA0_40") (pintype "bidirectional"))
      (node (ref "PA0") (pin "1") (pinfunction "1_1") (pintype "passive"))
    )
    (net (code "96") (name "S2.PA1") (class "Default")
      (node (ref "MOD1") (pin "39") (pinfunction "PA1_39") (pintype "bidirectional"))
      (node (ref "PA1") (pin "1") (pinfunction "1_1") (pintype "passive"))
    )
    (net (code "97") (name "S2.PA2") (class "Default")
      (node (ref "MOD1") (pin "38") (pinfunction "PA2_38") (pintype "bidirectional"))
      (node (ref "PA2") (pin "1") (pinfunction "1_1") (pintype "passive"))
    )
    (net (code "98") (name "S2.PA3") (class "Default")
      (node (ref "MOD1") (pin "37") (pinfunction "PA3_37") (pintype "bidirectional"))
      (node (ref "PA3") (pin "1") (pinfunction "1_1") (pintype "passive"))
    )
    (net (code "99") (name "S2.PA4") (class "Default")
      (node (ref "MOD1") (pin "36") (pinfunction "PA4_36") (pintype "bidirectional"))
      (node (ref "PA4") (pin "1") (pinfunction "1_1") (pintype "passive"))
    )
    (net (code "100") (name "S2.PA5") (class "Default")
      (node (ref "MOD1") (pin "35") (pinfunction "PA5_35") (pintype "bidirectional"))
      (node (ref "PA5") (pin "1") (pinfunction "1_1") (pintype "passive"))
    )
    (net (code "101") (name "S2.PA6") (class "Default")
      (node (ref "MOD1") (pin "34") (pinfunction "PA6_34") (pintype "bidirectional"))
      (node (ref "PA6") (pin "1") (pinfunction "1_1") (pintype "passive"))
    )
    (net (code "102") (name "S2.PA7") (class "Default")
      (node (ref "MOD1") (pin "33") (pinfunction "PA7_33") (pintype "bidirectional"))
      (node (ref "PA7") (pin "1") (pinfunction "1_1") (pintype "passive"))
    )
    (net (code "103") (name "S2.PA8") (class "Default")
      (node (ref "MOD1") (pin "22") (pinfunction "PA8_22") (pintype "bidirectional"))
      (node (ref "PA8") (pin "1") (pinfunction "1_1") (pintype "passive"))
    )
    (net (code "104") (name "S2.PA9") (class "Default")
      (node (ref "MOD1") (pin "23") (pinfunction "PA9_23") (pintype "bidirectional"))
      (node (ref "PA9") (pin "1") (pinfunction "1_1") (pintype "passive"))
    )
    (net (code "105") (name "S2.PA10") (class "Default")
      (node (ref "MOD1") (pin "24") (pinfunction "PA10_24") (pintype "bidirectional"))
      (node (ref "PA10") (pin "1") (pinfunction "1_1") (pintype "passive"))
    )
    (net (code "106") (name "S2.PA11") (class "Default")
      (node (ref "MOD1") (pin "25") (pinfunction "PA11_25") (pintype "bidirectional"))
      (node (ref "PA11") (pin "1") (pinfunction "1_1") (pintype "passive"))
    )
    (net (code "107") (name "S2.PA12") (class "Default")
      (node (ref "MOD1") (pin "26") (pinfunction "PA12_26") (pintype "bidirectional"))
      (node (ref "PA12") (pin "1") (pinfunction "1_1") (pintype "passive"))
    )
    (net (code "108") (name "S2.PA13") (class "Default")
      (node (ref "MOD1") (pin "27") (pinfunction "PA13_27") (pintype "bidirectional"))
      (node (ref "PA13") (pin "1") (pinfunction "1_1") (pintype "passive"))
    )
    (net (code "109") (name "S2.PA14") (class "Default")
      (node (ref "MOD1") (pin "28") (pinfunction "PA14_28") (pintype "bidirectional"))
      (node (ref "PA14") (pin "1") (pinfunction "1_1") (pintype "passive"))
    )
    (net (code "110") (name "S2.PA15") (class "Default")
      (node (ref "MOD1") (pin "29") (pinfunction "PA15_29") (pintype "bidirectional"))
      (node (ref "PA15") (pin "1") (pinfunction "1_1") (pintype "passive"))
    )
    (net (code "111") (name "S2.PB0") (class "Default")
      (node (ref "MOD1") (pin "1") (pinfunction "PB0_1") (pintype "bidirectional"))
      (node (ref "PB0") (pin "1") (pinfunction "1_1") (pintype "passive"))
    )
    (net (code "112") (name "S2.PB1") (class "Default")
      (node (ref "MOD1") (pin "2") (pinfunction "PB1_2") (pintype "bidirectional"))
      (node (ref "PB1") (pin "1") (pinfunction "1_1") (pintype "passive"))
    )
    (net (code "113") (name "S2.PB2") (class "Default")
      (node (ref "MOD1") (pin "3") (pinfunction "PB2_3") (pintype "bidirectional"))
      (node (ref "PB2") (pin "1") (pinfunction "1_1") (pintype "passive"))
    )
    (net (code "114") (name "S2.PB3") (class "Default")
      (node (ref "MOD1") (pin "4") (pinfunction "PB3_4") (pintype "bidirectional"))
      (node (ref "PB3") (pin "1") (pinfunction "1_1") (pintype "passive"))
    )
    (net (code "115") (name "S2.PB4") (class "Default")
      (node (ref "MOD1") (pin "5") (pinfunction "PB4_5") (pintype "bidirectional"))
      (node (ref "PB4") (pin "1") (pinfunction "1_1") (pintype "passive"))
    )
    (net (code "116") (name "S2.PB5") (class "Default")
      (node (ref "MOD1") (pin "6") (pinfunction "PB5_6") (pintype "bidirectional"))
      (node (ref "PB5") (pin "1") (pinfunction "1_1") (pintype "passive"))
    )
    (net (code "117") (name "S2.PB6") (class "Default")
      (node (ref "MOD1") (pin "7") (pinfunction "PB6_7") (pintype "bidirectional"))
      (node (ref "PB6") (pin "1") (pinfunction "1_1") (pintype "passive"))
    )
    (net (code "118") (name "S2.PB7") (class "Default")
      (node (ref "MOD1") (pin "8") (pinfunction "PB7_8") (pintype "bidirectional"))
      (node (ref "PB7") (pin "1") (pinfunction "1_1") (pintype "passive"))
    )
    (net (code "119") (name "S2.PB8") (class "Default")
      (node (ref "MOD1") (pin "14") (pinfunction "PB8_14") (pintype "bidirectional"))
      (node (ref "PB8") (pin "1") (pinfunction "1_1") (pintype "passive"))
    )
    (net (code "120") (name "S2.PB9") (class "Default")
      (node (ref "MOD1") (pin "15") (pinfunction "PB9_15") (pintype "bidirectional"))
      (node (ref "PB9") (pin "1") (pinfunction "1_1") (pintype "passive"))
    )
    (net (code "121") (name "S2.PB10") (class "Default")
      (node (ref "MOD1") (pin "16") (pinfunction "PB10_16") (pintype "bidirectional"))
      (node (ref "PB10") (pin "1") (pinfunction "1_1") (pintype "passive"))
    )
    (net (code "122") (name "S2.PB11") (class "Default")
      (node (ref "MOD1") (pin "17") (pinfunction "PB11_17") (pintype "bidirectional"))
      (node (ref "PB11") (pin "1") (pinfunction "1_1") (pintype "passive"))
    )
    (net (code "123") (name "S2.PB12") (class "Default")
      (node (ref "MOD1") (pin "18") (pinfunction "PB12_18") (pintype "bidirectional"))
      (node (ref "PB12") (pin "1") (pinfunction "1_1") (pintype "passive"))
    )
    (net (code "124") (name "S2.PB13") (class "Default")
      (node (ref "MOD1") (pin "19") (pinfunction "PB13_19") (pintype "bidirectional"))
      (node (ref "PB13") (pin "1") (pinfunction "1_1") (pintype "passive"))
    )
    (net (code "125") (name "S2.PB14") (class "Default")
      (node (ref "MOD1") (pin "20") (pinfunction "PB14_20") (pintype "bidirectional"))
      (node (ref "PB14") (pin "1") (pinfunction "1_1") (pintype "passive"))
    )
    (net (code "126") (name "S2.PB15") (class "Default")
      (node (ref "MOD1") (pin "21") (pinfunction "PB15_21") (pintype "bidirectional"))
      (node (ref "PB15") (pin "1") (pinfunction "1_1") (pintype "passive"))
    )
    (net (code "127") (name "S2.VBAT") (class "Default")
      (node (ref "G1") (pin "+") (pinfunction "+_+") (pintype "passive"))
      (node (ref "MOD1") (pin "32") (pinfunction "VBAT_32") (pintype "power_in"))
      (node (ref "VBAT") (pin "1") (pinfunction "1_1") (pintype "passive"))
    )
    (net (code "128") (name "S3.AIN1") (class "Default")
      (node (ref "C29") (pin "1") (pinfunction "1_1") (pintype "passive"))
      (node (ref "IC3") (pin "10") (pinfunction "PA0/WKUP/USART2_CTS/ADC12_IN0/TIM2_CH1_ETR_10") (pintype "bidirectional"))
      (node (ref "R29") (pin "1") (pinfunction "1_1") (pintype "passive"))
      (node (ref "R30") (pin "2") (pinfunction "2_2") (pintype "passive"))
      (node (ref "R38") (pin "1") (pinfunction "1_1") (pintype "passive"))
    )
    (net (code "129") (name "S3.LED") (class "Default")
      (node (ref "IC3") (pin "30") (pinfunction "PA9/USART1_TX/TIM1_CH2_30") (pintype "bidirectional"))
      (node (ref "R34") (pin "1") (pinfunction "1_1") (pintype "passive"))
      (node (ref "R35") (pin "1") (pinfunction "1_1") (pintype "passive"))
    )
    (net (code "130") (name "S3.M25_CS") (class "Default")
      (node (ref "IC3") (pin "11") (pinfunction "PA1/USART2_RTS/ADC12_IN1/TIM2_CH2_11") (pintype "bidirectional"))
    )
    (net (code "131") (name "S3.OSC_IN") (class "Default")
      (node (ref "C11") (pin "1") (pinfunction "1_1") (pintype "passive"))
      (node (ref "IC3") (pin "5") (pinfunction "OSC_IN/(PD0/CANRX)_5") (pintype "input"))
      (node (ref "Q2") (pin "1") (pinfunction "1_1") (pintype "passive"))
    )
    (net (code "132") (name "S3.OSC_OUT") (class "Default")
      (node (ref "C12") (pin "1") (pinfunction "1_1") (pintype "passive"))
      (node (ref "IC3") (pin "6") (pinfunction "OSC_OUT/(PD1/CANTX)_6") (pintype "output"))
      (node (ref "Q2") (pin "2") (pinfunction "2_2") (pintype "passive"))
    )
    (net (code "133") (name "S3.SWCLK") (class "Default")
      (node (ref "IC3") (pin "37") (pinfunction "JTCK-SWCLK/(PA14)_37") (pintype "bidirectional"))
      (node (ref "JP1") (pin "2") (pinfunction "2_2") (pintype "passive"))
    )
    (net (code "134") (name "S3.SWDIO") (class "Default")
      (node (ref "IC3") (pin "34") (pinfunction "JTMS-SWDIO/(PA13)_34") (pintype "bidirectional"))
      (node (ref "JP1") (pin "4") (pinfunction "4_4") (pintype "passive"))
    )
    (net (code "135") (name "S3.SWIM") (class "Default")
      (node (ref "IC3") (pin "22") (pinfunction "PB11/I2C2_SDA/USART3_RX/(TIM2_CH4)_22") (pintype "bidirectional"))
      (node (ref "IC3") (pin "45") (pinfunction "PB8/TIM4_CH3/(I2C1_SCL/CANRX)_45") (pintype "bidirectional"))
    )
    (net (code "136") (name "S3.SWIM_IN") (class "Default")
      (node (ref "IC3") (pin "21") (pinfunction "PB10/I2C2_SCL/USART3_TX/(TIM2_CH3)_21") (pintype "bidirectional"))
      (node (ref "IC3") (pin "43") (pinfunction "PB7/I2C1_SDA/TIM4_CH2/(USART1_RX)_43") (pintype "bidirectional"))
      (node (ref "IC3") (pin "46") (pinfunction "PB9/TIM4_CH4/(I2C1_SDA/CANTX)_46") (pintype "bidirectional"))
    )
    (net (code "137") (name "S3.SWIM_RST") (class "Default")
      (node (ref "IC3") (pin "42") (pinfunction "PB6/I2C1_SCL/TIM4_CH1/(USART1_TX)_42") (pintype "bidirectional"))
      (node (ref "R37") (pin "2") (pinfunction "2_2") (pintype "passive"))
    )
    (net (code "138") (name "S3.SWIM_RST_IN") (class "Default")
      (node (ref "IC3") (pin "41") (pinfunction "PB5/I2C1_SMBA/(TIM3_CH2/SPI1_MOSI)_41") (pintype "bidirectional"))
      (node (ref "R37") (pin "1") (pinfunction "1_1") (pintype "passive"))
    )
    (net (code "139") (name "S3.T_JTCK") (class "Default")
      (node (ref "IC3") (pin "15") (pinfunction "PA5/SPI1_SCK/ADC12_IN5_15") (pintype "bidirectional"))
      (node (ref "IC3") (pin "26") (pinfunction "PB13/SPI2_SCK/TIM1_CH1N/USART3_CTS_26") (pintype "bidirectional"))
      (node (ref "R22") (pin "1") (pinfunction "1_1") (pintype "passive"))
    )
    (net (code "140") (name "S3.T_JTDI") (class "Default")
      (node (ref "IC3") (pin "17") (pinfunction "PA7SPI1_MOSI/ADC12_IN7/TIM3_CH2_17") (pintype "bidirectional"))
    )
    (net (code "141") (name "S3.T_JTDO") (class "Default")
      (node (ref "IC3") (pin "16") (pinfunction "PA6/SPI1_MISO/ADC12_IN6/TIM3_CH1_16") (pintype "bidirectional"))
    )
    (net (code "142") (name "S3.T_JTMS") (class "Default")
      (node (ref "IC3") (pin "27") (pinfunction "PB14/SPI2_MISO/TIM1_CH2N/USART3_RTS_27") (pintype "bidirectional"))
      (node (ref "R19") (pin "1") (pinfunction "1_1") (pintype "passive"))
      (node (ref "R23") (pin "1") (pinfunction "1_1") (pintype "passive"))
    )
    (net (code "143") (name "S3.T_NRST") (class "Default")
      (node (ref "IC3") (pin "18") (pinfunction "PB0/ADC12_IN8/TIM3_CH3/(TIM1_CH2N)_18") (pintype "bidirectional"))
      (node (ref "R25") (pin "1") (pinfunction "1_1") (pintype "passive"))
    )
    (net (code "144") (name "S3.T_SWDIO_IN") (class "Default")
      (node (ref "IC3") (pin "25") (pinfunction "PB12/SPI2_NSS/I2C2_SMBAI/TIM1_BKIN/USART3_CK_25") (pintype "bidirectional"))
      (node (ref "R19") (pin "2") (pinfunction "2_2") (pintype "passive"))
    )
    (net (code "145") (name "S3.T_SWO") (class "Default")
      (node (ref "IC3") (pin "31") (pinfunction "PA10/USART1_RX/TIM1_CH3_31") (pintype "bidirectional"))
      (node (ref "R24") (pin "1") (pinfunction "1_1") (pintype "passive"))
    )
    (net (code "146") (name "S3.U2_CK") (class "Default")
      (node (ref "IC3") (pin "14") (pinfunction "PA4/SPI1_NSS/ADC12_IN4/USART2_CK_14") (pintype "bidirectional"))
    )
    (net (code "147") (name "S3.U2_RX") (class "Default")
      (node (ref "IC3") (pin "13") (pinfunction "PA3/USART2_RX/ADC12_IN3/TIM2_CH4_13") (pintype "bidirectional"))
    )
    (net (code "148") (name "S3.U2_TX") (class "Default")
      (node (ref "IC3") (pin "12") (pinfunction "PA2/USART2_TX/ADC12_IN2/TIM2_CH3_12") (pintype "bidirectional"))
    )
    (net (code "149") (name "S3.USBDM") (class "Default")
      (node (ref "IC3") (pin "32") (pinfunction "PA11/CANRX/USBDM/USART1_CTS/TIM1_CH4_32") (pintype "bidirectional"))
      (node (ref "R27") (pin "1") (pinfunction "1_1") (pintype "passive"))
    )
    (net (code "150") (name "S3.USBDP") (class "Default")
      (node (ref "IC3") (pin "33") (pinfunction "PA12/CANTX/USBDP/USART1_RTS/TIM1_ETR_33") (pintype "bidirectional"))
      (node (ref "R26") (pin "1") (pinfunction "1_1") (pintype "passive"))
    )
    (net (code "151") (name "SWCLK") (class "Default")
      (node (ref "R22") (pin "2") (pinfunction "2_2") (pintype "passive"))
      (node (ref "R7") (pin "2") (pinfunction "2_2") (pintype "passive"))
      (node (ref "SWD1") (pin "2") (pinfunction "2_2") (pintype "passive"))
      (node (ref "SWD2") (pin "2") (pinfunction "2_2") (pintype "passive"))
    )
    (net (code "152") (name "SWDIO") (class "Default")
      (node (ref "R23") (pin "2") (pinfunction "2_2") (pintype "passive"))
      (node (ref "R8") (pin "2") (pinfunction "2_2") (pintype "passive"))
      (node (ref "SWD1") (pin "4") (pinfunction "4_4") (pintype "passive"))
      (node (ref "SWD2") (pin "4") (pinfunction "4_4") (pintype "passive"))
    )
    (net (code "153") (name "SWO") (class "Default")
      (node (ref "R24") (pin "2") (pinfunction "2_2") (pintype "passive"))
      (node (ref "R9") (pin "2") (pinfunction "2_2") (pintype "passive"))
      (node (ref "SWD1") (pin "6") (pinfunction "6_6") (pintype "passive"))
      (node (ref "SWD2") (pin "6") (pinfunction "6_6") (pintype "passive"))
    )
    (net (code "154") (name "VBAT") (class "Default")
      (node (ref "IC1") (pin "1") (pinfunction "VBAT_1") (pintype "power_in"))
      (node (ref "J1") (pin "32") (pinfunction "12_32") (pintype "passive"))
    )
    (net (code "155") (name "VCC") (class "Default")
      (node (ref "C13") (pin "1") (pinfunction "1_1") (pintype "passive"))
      (node (ref "C14") (pin "1") (pinfunction "1_1") (pintype "passive"))
      (node (ref "C15") (pin "1") (pinfunction "1_1") (pintype "passive"))
      (node (ref "C16") (pin "1") (pinfunction "1_1") (pintype "passive"))
      (node (ref "C20") (pin "1") (pinfunction "1_1") (pintype "passive"))
      (node (ref "C21") (pin "+") (pinfunction "+_+") (pintype "passive"))
      (node (ref "IC3") (pin "1") (pinfunction "VBAT_1") (pintype "power_in"))
      (node (ref "IC3") (pin "24") (pinfunction "VDD_24") (pintype "power_in"))
      (node (ref "IC3") (pin "36") (pinfunction "VDD_36") (pintype "power_in"))
      (node (ref "IC3") (pin "48") (pinfunction "VDD_48") (pintype "power_in"))
      (node (ref "IC3") (pin "9") (pinfunction "VDDA_9") (pintype "power_in"))
      (node (ref "JP1") (pin "1") (pinfunction "1_1") (pintype "passive"))
      (node (ref "LED4") (pin "A") (pinfunction "A_A") (pintype "passive"))
      (node (ref "R20") (pin "2") (pinfunction "2_2") (pintype "passive"))
      (node (ref "R28") (pin "2") (pinfunction "2_2") (pintype "passive"))
      (node (ref "R29") (pin "2") (pinfunction "2_2") (pintype "passive"))
      (node (ref "R33") (pin "1") (pinfunction "1_1") (pintype "passive"))
      (node (ref "U1") (pin "2") (pinfunction "OUT_2") (pintype "power_in"))
    )
    (net (code "156") (name "unconnected-(IC2-VREF-Pad5)") (class "Default")
      (node (ref "IC2") (pin "5") (pinfunction "VREF_5") (pintype "passive"))
    )
    (net (code "157") (name "unconnected-(IC3-JTDI{slash}(TIM2_CH1_ETR{slash}PA15{slash}SPI1_NSS)-Pad38)") (class "Default")
      (node (ref "IC3") (pin "38") (pinfunction "JTDI/(TIM2_CH1_ETR/PA15/SPI1_NSS)_38") (pintype "bidirectional"))
    )
    (net (code "158") (name "unconnected-(IC3-JTDO{slash}(TIM2_CH2{slash}PB3{slash}TRACESWO{slash}SPI1_SCK)-Pad39)") (class "Default")
      (node (ref "IC3") (pin "39") (pinfunction "JTDO/(TIM2_CH2/PB3/TRACESWO/SPI1_SCK)_39") (pintype "bidirectional"))
    )
    (net (code "159") (name "unconnected-(IC3-JTNRST{slash}(PB4{slash}TIM3_CH1{slash}SPI1_MISO)-Pad40)") (class "Default")
      (node (ref "IC3") (pin "40") (pinfunction "JTNRST/(PB4/TIM3_CH1/SPI1_MISO)_40") (pintype "bidirectional"))
    )
    (net (code "160") (name "unconnected-(IC3-PB1{slash}ADC12_IN9{slash}TIM3_CH4{slash}(TIM1_CH3N)-Pad19)") (class "Default")
      (node (ref "IC3") (pin "19") (pinfunction "PB1/ADC12_IN9/TIM3_CH4/(TIM1_CH3N)_19") (pintype "bidirectional"))
    )
    (net (code "161") (name "unconnected-(IC3-PB15{slash}SPI2_MOSI{slash}TIM1_CH3N-Pad28)") (class "Default")
      (node (ref "IC3") (pin "28") (pinfunction "PB15/SPI2_MOSI/TIM1_CH3N_28") (pintype "bidirectional"))
    )
    (net (code "162") (name "unconnected-(IC3-PC15{slash}OSC32_OUT-Pad4)") (class "Default")
      (node (ref "IC3") (pin "4") (pinfunction "PC15/OSC32_OUT_4") (pintype "bidirectional"))
    )
    (net (code "163") (name "unconnected-(U1-MASS-Pad4)") (class "Default")
      (node (ref "U1") (pin "4") (pinfunction "MASS_4") (pintype "passive"))
    )
    (net (code "164") (name "~{RESET}") (class "Default")
      (node (ref "C1") (pin "1") (pinfunction "1_1") (pintype "passive"))
      (node (ref "IC1") (pin "7") (pinfunction "~{RESET}_7") (pintype "input"))
      (node (ref "J1") (pin "9") (pinfunction "9_9") (pintype "passive"))
      (node (ref "R1") (pin "1") (pinfunction "1_1") (pintype "passive"))
      (node (ref "R25") (pin "2") (pinfunction "2_2") (pintype "passive"))
      (node (ref "SW1") (pin "2") (pinfunction "S_2") (pintype "passive"))
      (node (ref "SWD1") (pin "5") (pinfunction "5_5") (pintype "passive"))
      (node (ref "SWD2") (pin "5") (pinfunction "5_5") (pintype "passive"))
    )
    (net (code "165") (name "~{S2.RESET}") (class "Default")
      (node (ref "MOD1") (pin "9") (pinfunction "~{RESET}_9") (pintype "input"))
      (node (ref "RST") (pin "1") (pinfunction "1_1") (pintype "passive"))
    )
    (net (code "166") (name "~{S3.RESET}") (class "Default")
      (node (ref "C17") (pin "1") (pinfunction "1_1") (pintype "passive"))
      (node (ref "IC3") (pin "7") (pinfunction "~{RESET}_7") (pintype "input"))
      (node (ref "R20") (pin "1") (pinfunction "1_1") (pintype "passive"))
    )
  )
)
